# RK05exNew.net
KiCad netlist of a schematic drawn in EAGLE
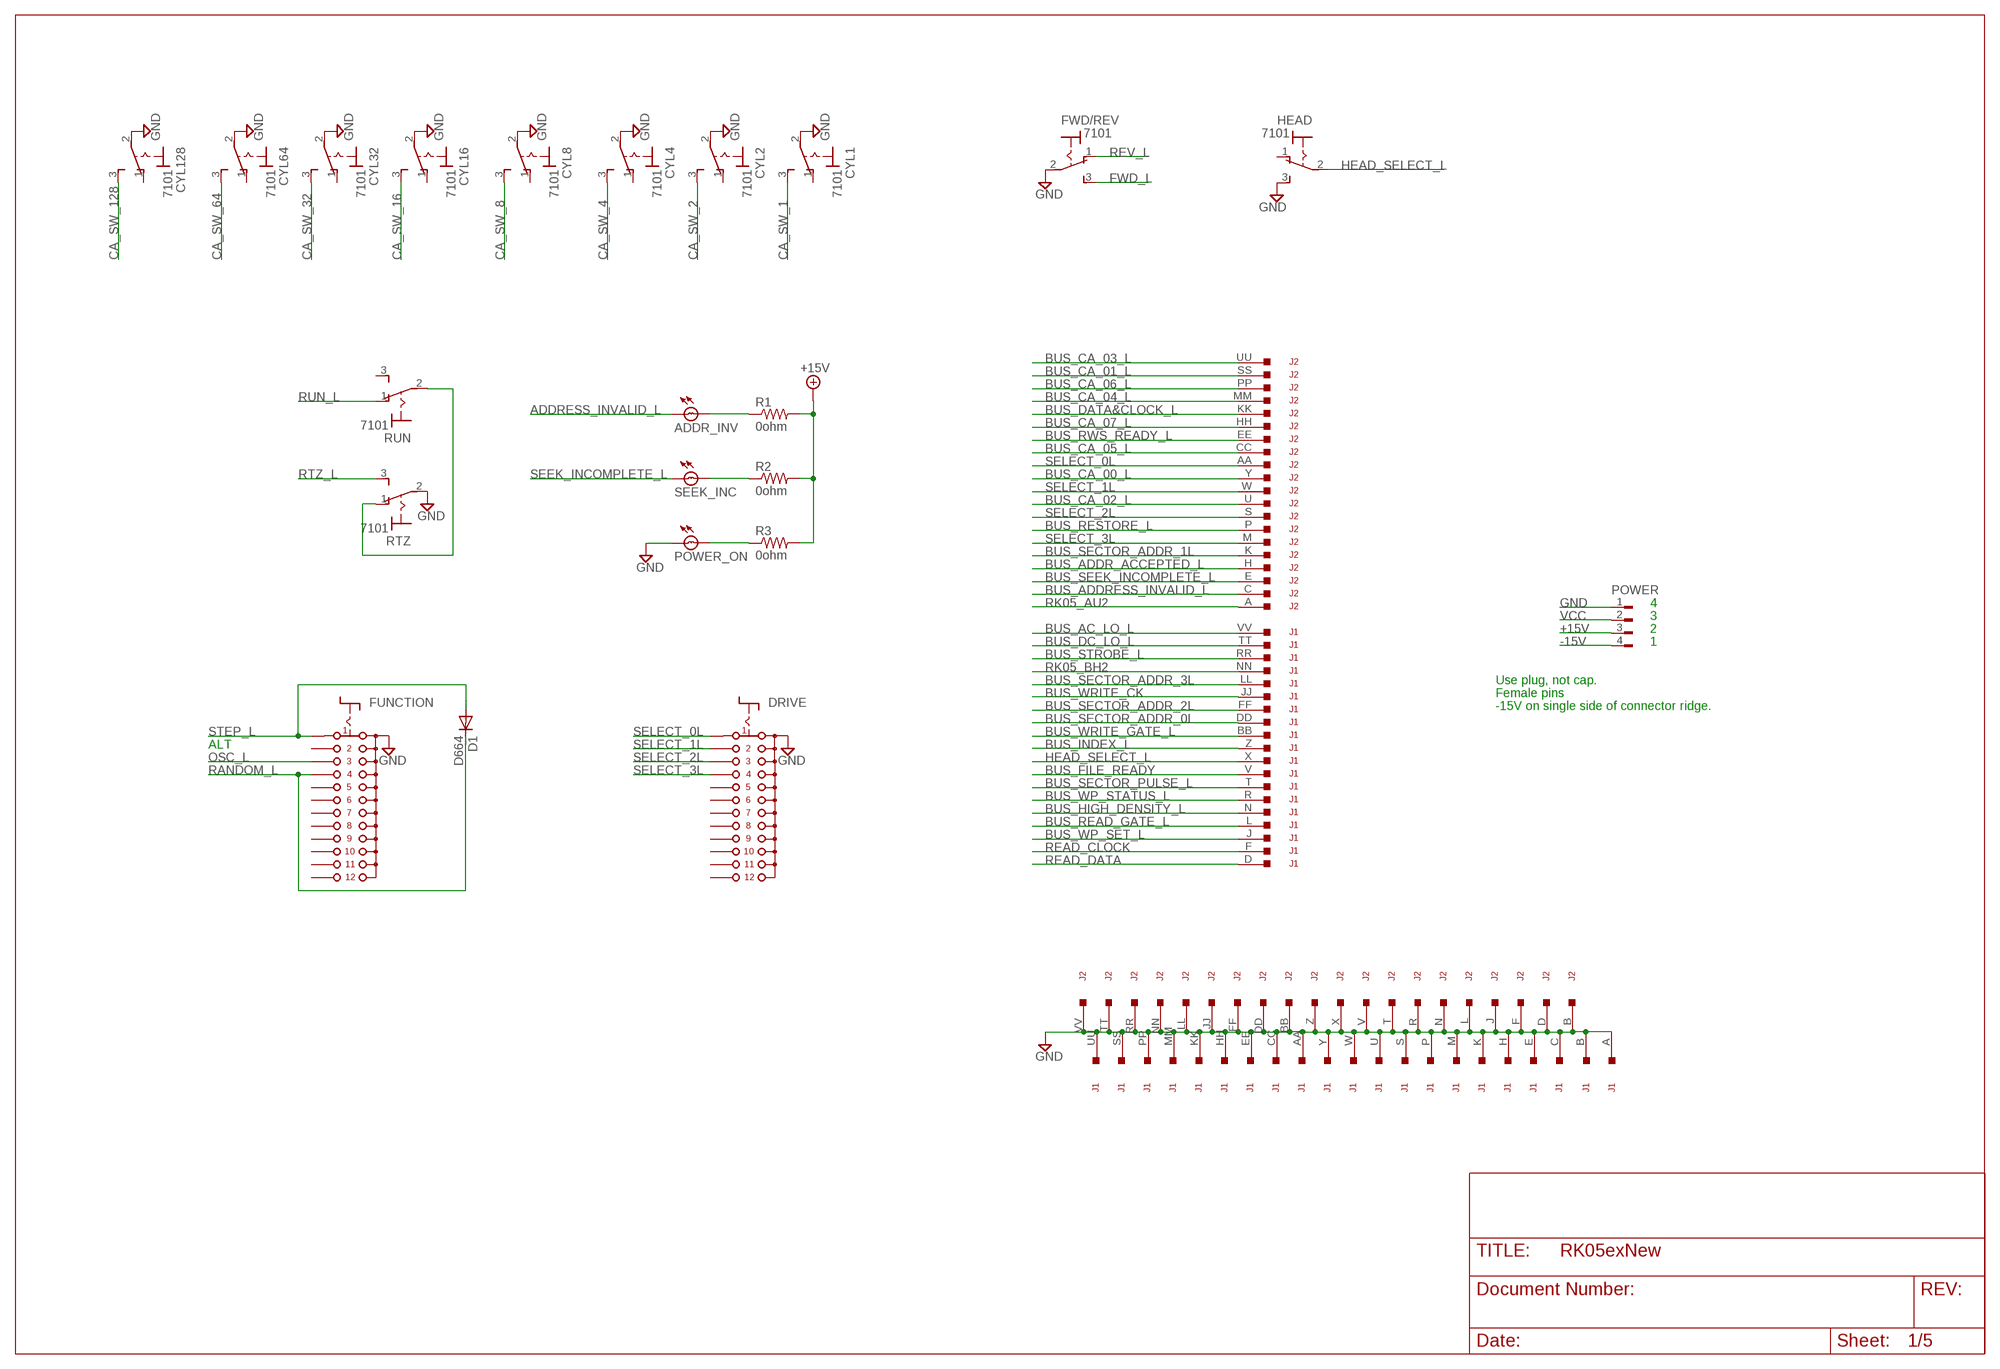
[diagram p0: schematic, sheet 1]
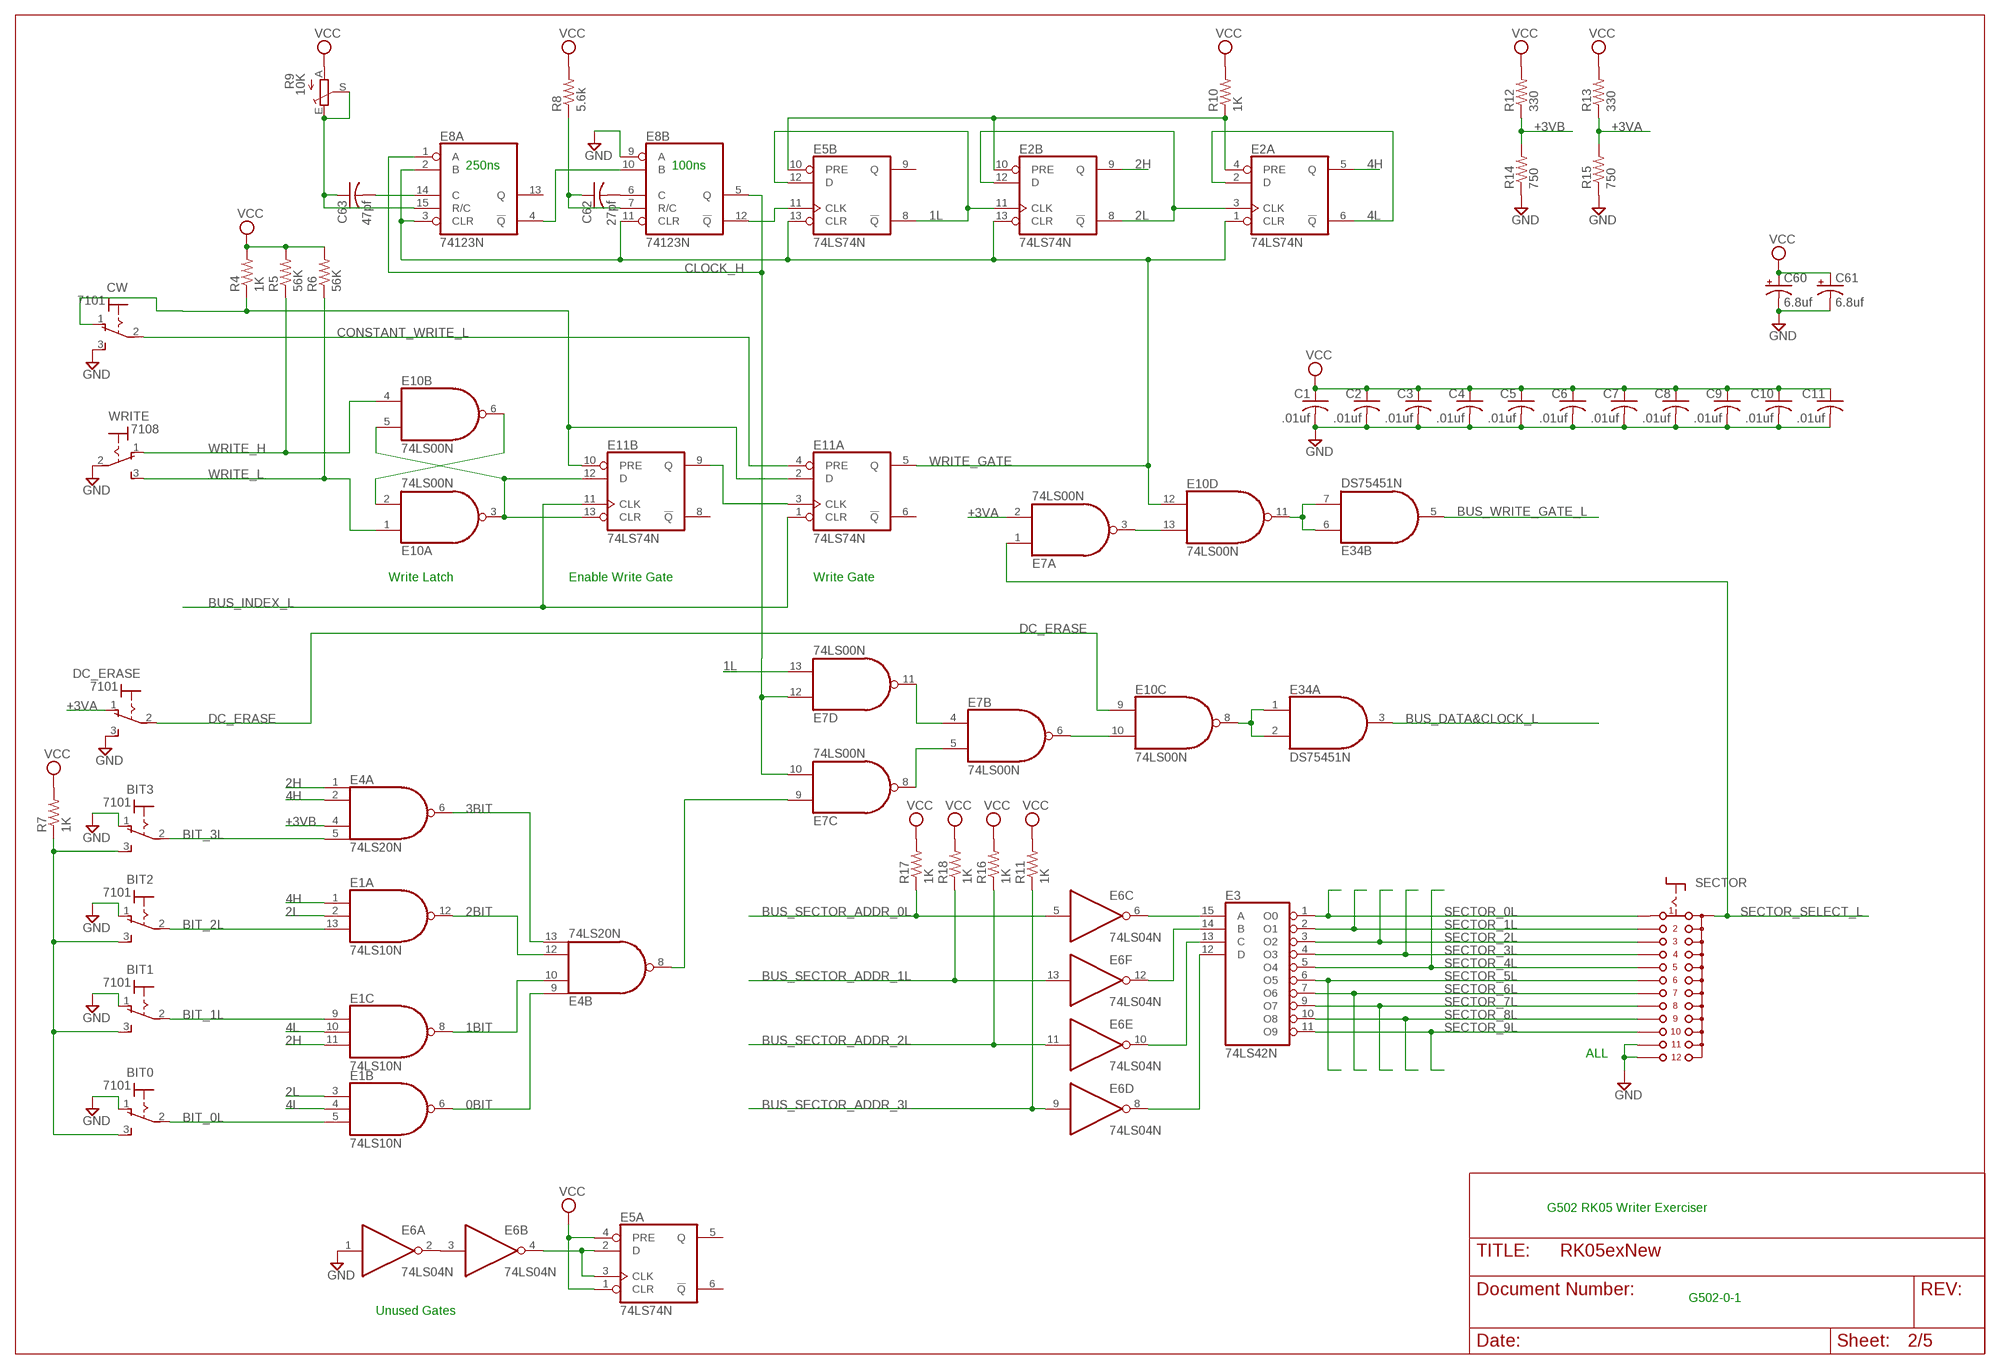
[diagram p1: schematic, sheet 2]
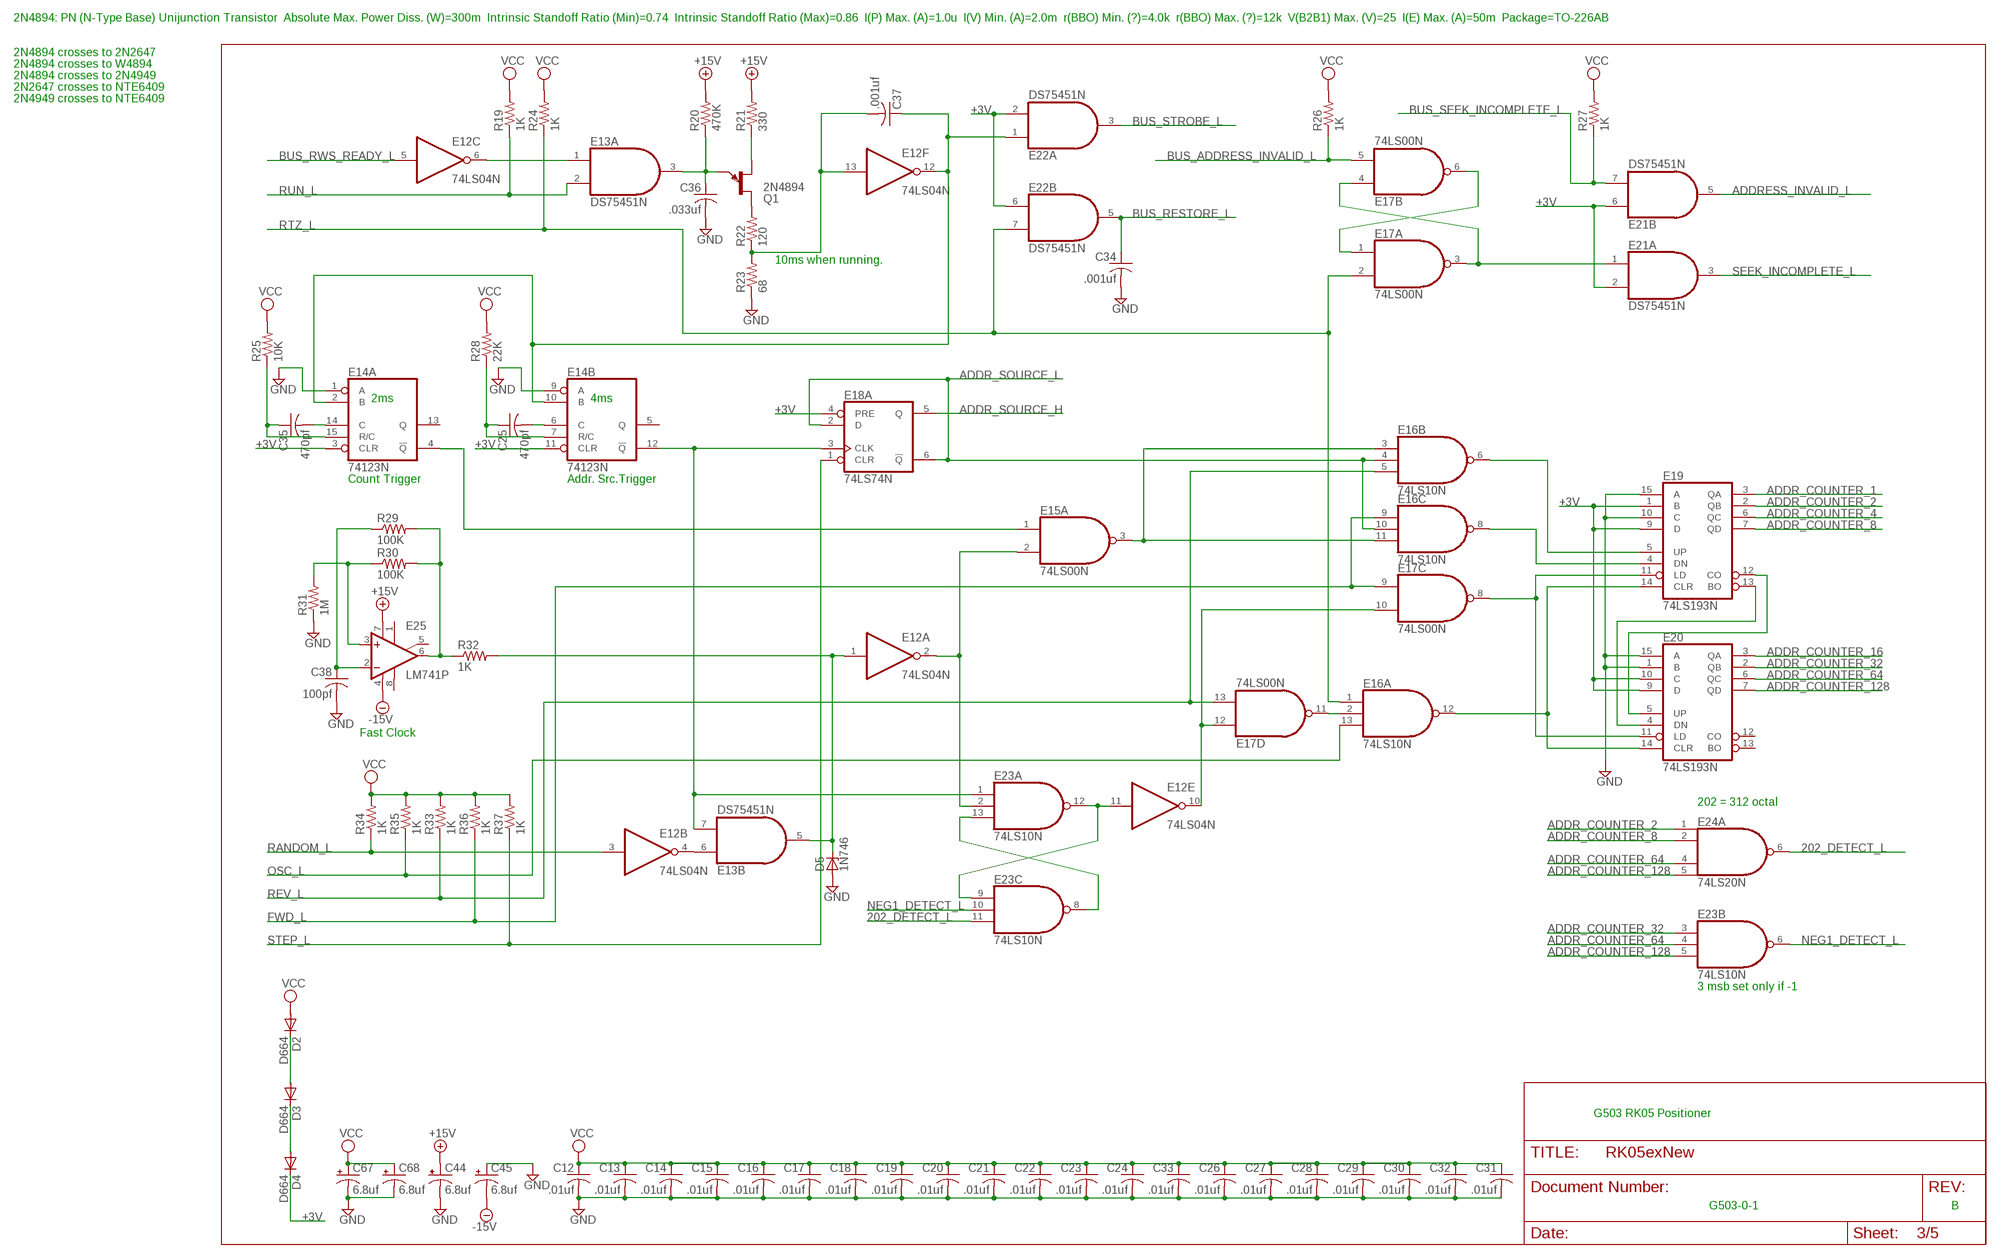
[diagram p2: schematic, sheet 3]
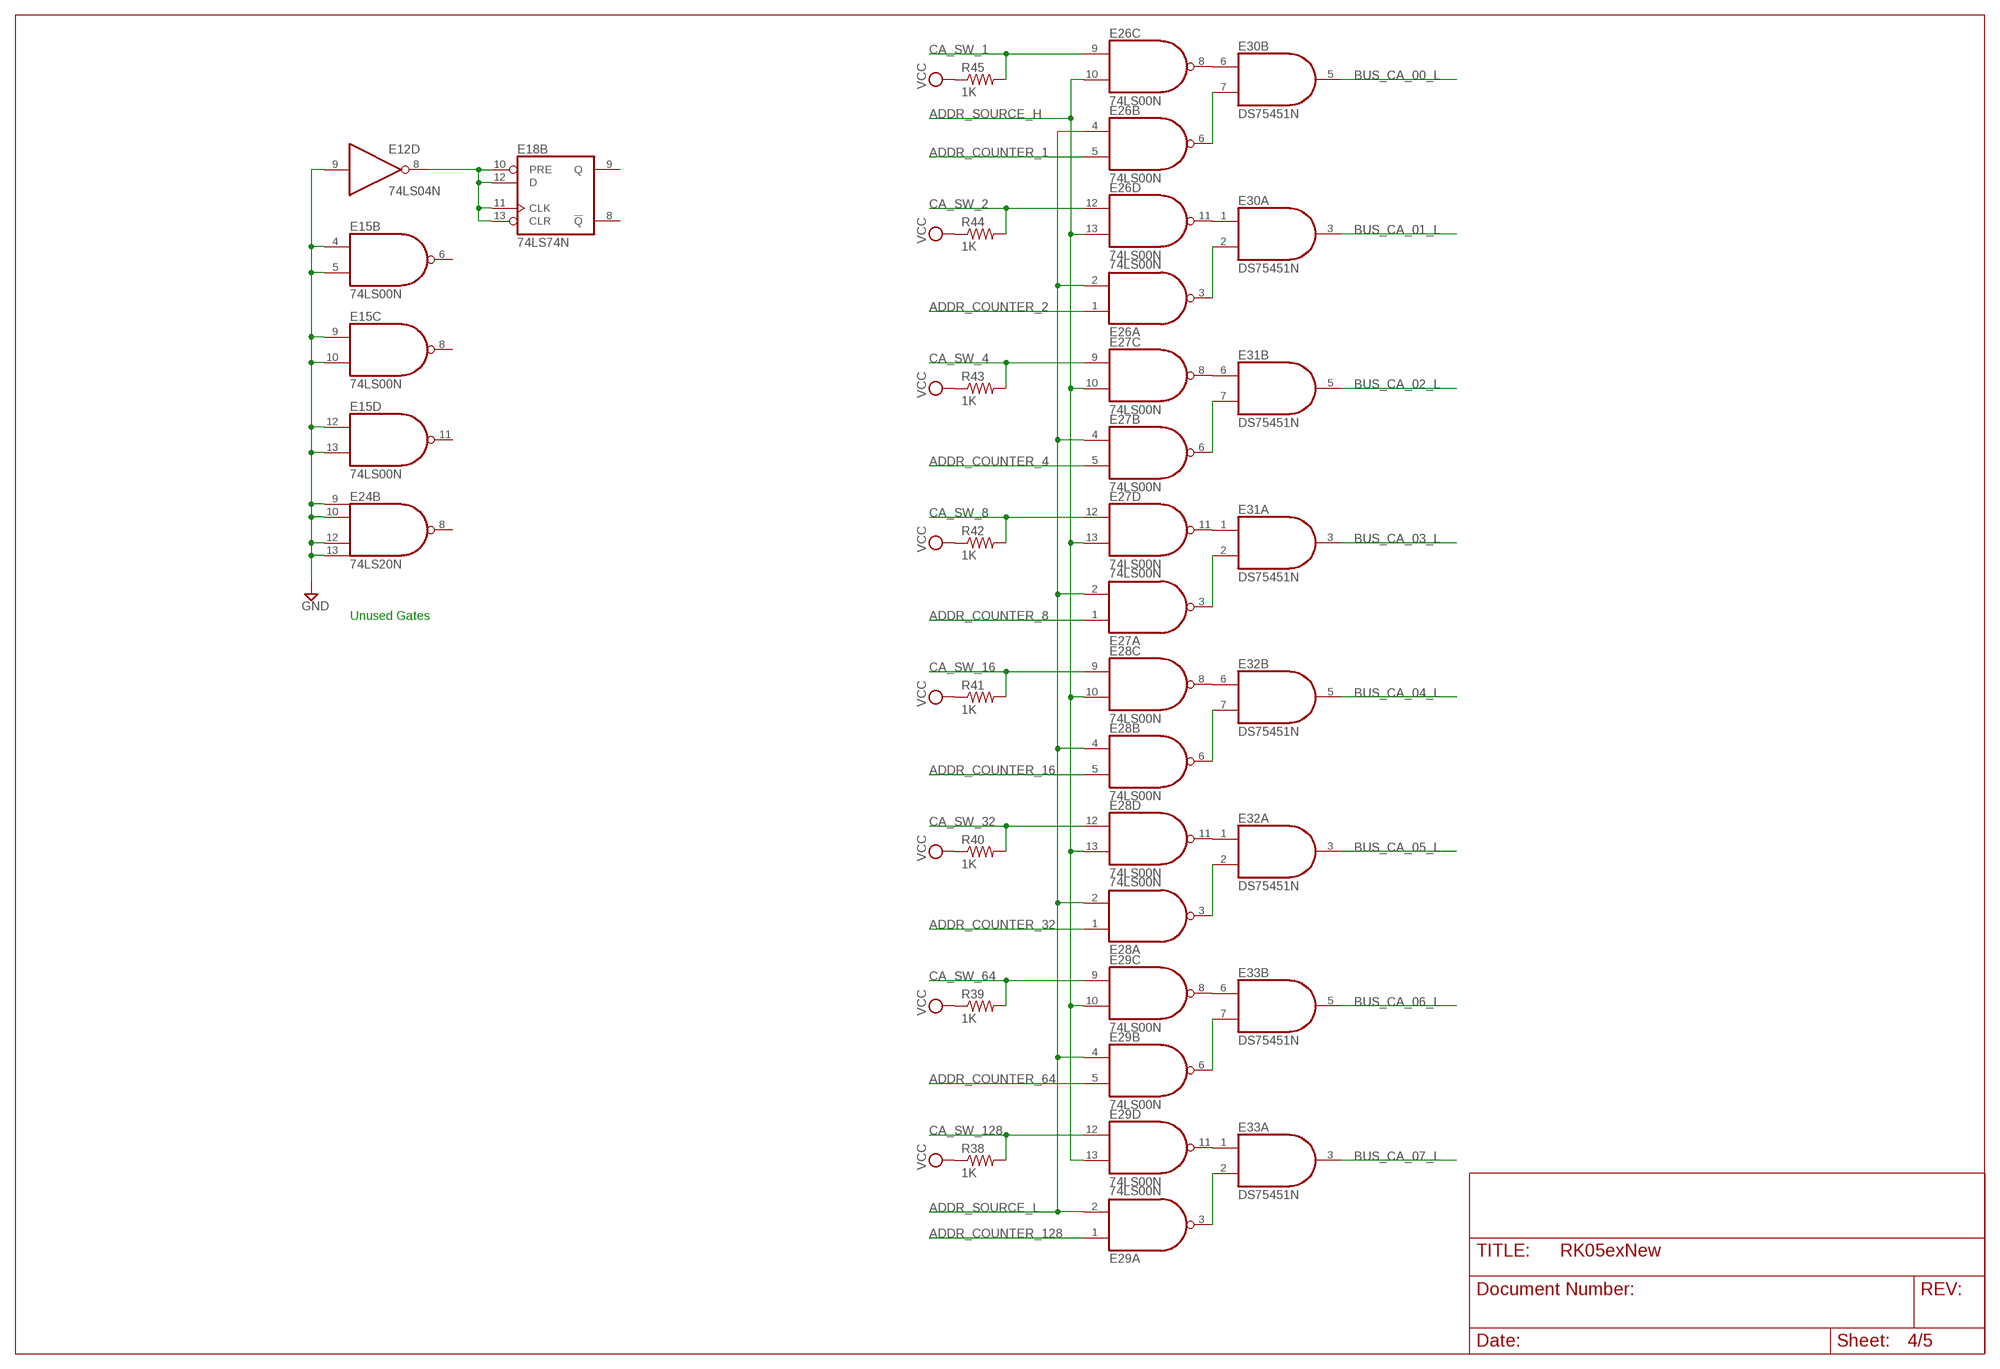
[diagram p3: schematic, sheet 4]
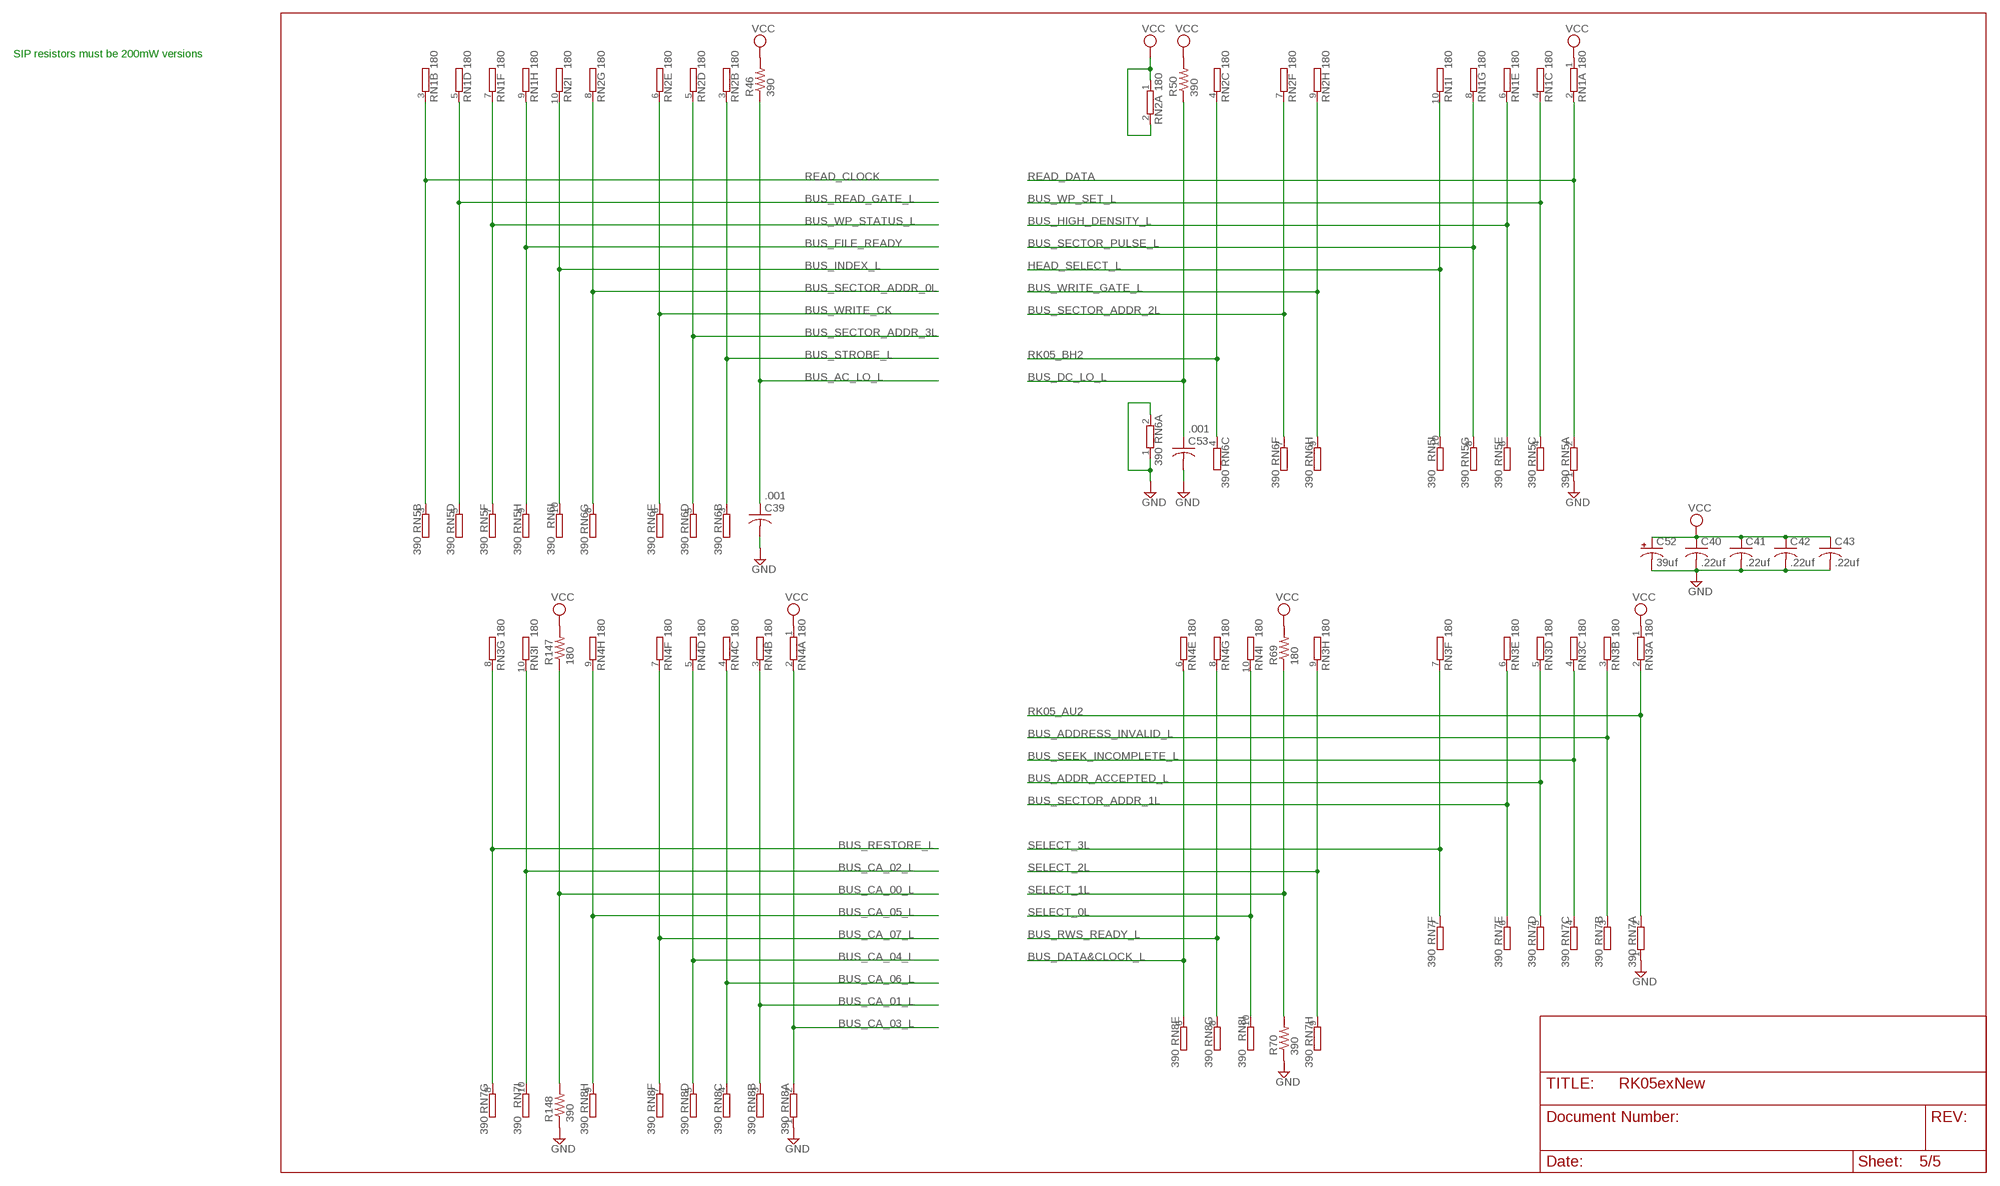
[diagram p4: schematic, sheet 5]

(export (version "E")
  (design (tool "Eeschema 10.0.6"))
  (components
    (comp (ref "E12")
      (value "74LS04N")
      (footprint "eagle-import:DIL14")
      (libsource (lib "eagle-import") (part "7404NLS"))
    )
    (comp (ref "E15")
      (value "74LS00N")
      (footprint "eagle-import:DIL14")
      (libsource (lib "eagle-import") (part "7400NLS"))
    )
    (comp (ref "E18")
      (value "74LS74N")
      (footprint "eagle-import:DIL14")
      (libsource (lib "eagle-import") (part "7474NLS"))
    )
    (comp (ref "E24")
      (value "74LS20N")
      (footprint "eagle-import:DIL14")
      (libsource (lib "eagle-import") (part "7420NLS"))
    )
    (comp (ref "E26")
      (value "74LS00N")
      (footprint "eagle-import:DIL14")
      (libsource (lib "eagle-import") (part "7400NLS"))
    )
    (comp (ref "E27")
      (value "74LS00N")
      (footprint "eagle-import:DIL14")
      (libsource (lib "eagle-import") (part "7400NLS"))
    )
    (comp (ref "E28")
      (value "74LS00N")
      (footprint "eagle-import:DIL14")
      (libsource (lib "eagle-import") (part "7400NLS"))
    )
    (comp (ref "E29")
      (value "74LS00N")
      (footprint "eagle-import:DIL14")
      (libsource (lib "eagle-import") (part "7400NLS"))
    )
    (comp (ref "E30")
      (value "DS75451N")
      (footprint "eagle-import:DIL08")
      (libsource (lib "eagle-import") (part "DS75451N"))
    )
    (comp (ref "E31")
      (value "DS75451N")
      (footprint "eagle-import:DIL08")
      (libsource (lib "eagle-import") (part "DS75451N"))
    )
    (comp (ref "E32")
      (value "DS75451N")
      (footprint "eagle-import:DIL08")
      (libsource (lib "eagle-import") (part "DS75451N"))
    )
    (comp (ref "E33")
      (value "DS75451N")
      (footprint "eagle-import:DIL08")
      (libsource (lib "eagle-import") (part "DS75451N"))
    )
    (comp (ref "R38")
      (value "1K")
      (footprint "eagle-import:0207_10")
      (libsource (lib "eagle-import") (part "R-US_0207/10"))
    )
    (comp (ref "R39")
      (value "1K")
      (footprint "eagle-import:0207_10")
      (libsource (lib "eagle-import") (part "R-US_0207/10"))
    )
    (comp (ref "R40")
      (value "1K")
      (footprint "eagle-import:0207_10")
      (libsource (lib "eagle-import") (part "R-US_0207/10"))
    )
    (comp (ref "R41")
      (value "1K")
      (footprint "eagle-import:0207_10")
      (libsource (lib "eagle-import") (part "R-US_0207/10"))
    )
    (comp (ref "R42")
      (value "1K")
      (footprint "eagle-import:0207_10")
      (libsource (lib "eagle-import") (part "R-US_0207/10"))
    )
    (comp (ref "R43")
      (value "1K")
      (footprint "eagle-import:0207_10")
      (libsource (lib "eagle-import") (part "R-US_0207/10"))
    )
    (comp (ref "R44")
      (value "1K")
      (footprint "eagle-import:0207_10")
      (libsource (lib "eagle-import") (part "R-US_0207/10"))
    )
    (comp (ref "R45")
      (value "1K")
      (footprint "eagle-import:0207_10")
      (libsource (lib "eagle-import") (part "R-US_0207/10"))
    )
    (comp (ref "C12")
      (value ".01uf")
      (footprint "eagle-import:C075-032X103")
      (libsource (lib "eagle-import") (part "C-US075-032X103"))
    )
    (comp (ref "C13")
      (value ".01uf")
      (footprint "eagle-import:C075-032X103")
      (libsource (lib "eagle-import") (part "C-US075-032X103"))
    )
    (comp (ref "C14")
      (value ".01uf")
      (footprint "eagle-import:C075-032X103")
      (libsource (lib "eagle-import") (part "C-US075-032X103"))
    )
    (comp (ref "C15")
      (value ".01uf")
      (footprint "eagle-import:C075-032X103")
      (libsource (lib "eagle-import") (part "C-US075-032X103"))
    )
    (comp (ref "C16")
      (value ".01uf")
      (footprint "eagle-import:C075-032X103")
      (libsource (lib "eagle-import") (part "C-US075-032X103"))
    )
    (comp (ref "C17")
      (value ".01uf")
      (footprint "eagle-import:C075-032X103")
      (libsource (lib "eagle-import") (part "C-US075-032X103"))
    )
    (comp (ref "C18")
      (value ".01uf")
      (footprint "eagle-import:C075-032X103")
      (libsource (lib "eagle-import") (part "C-US075-032X103"))
    )
    (comp (ref "C19")
      (value ".01uf")
      (footprint "eagle-import:C075-032X103")
      (libsource (lib "eagle-import") (part "C-US075-032X103"))
    )
    (comp (ref "C20")
      (value ".01uf")
      (footprint "eagle-import:C075-032X103")
      (libsource (lib "eagle-import") (part "C-US075-032X103"))
    )
    (comp (ref "C21")
      (value ".01uf")
      (footprint "eagle-import:C075-032X103")
      (libsource (lib "eagle-import") (part "C-US075-032X103"))
    )
    (comp (ref "C22")
      (value ".01uf")
      (footprint "eagle-import:C075-032X103")
      (libsource (lib "eagle-import") (part "C-US075-032X103"))
    )
    (comp (ref "C23")
      (value ".01uf")
      (footprint "eagle-import:C075-032X103")
      (libsource (lib "eagle-import") (part "C-US075-032X103"))
    )
    (comp (ref "C24")
      (value ".01uf")
      (footprint "eagle-import:C075-032X103")
      (libsource (lib "eagle-import") (part "C-US075-032X103"))
    )
    (comp (ref "C25")
      (value "470pf")
      (footprint "eagle-import:C075-032X103")
      (libsource (lib "eagle-import") (part "C-US075-032X103"))
    )
    (comp (ref "C26")
      (value ".01uf")
      (footprint "eagle-import:C075-032X103")
      (libsource (lib "eagle-import") (part "C-US075-032X103"))
    )
    (comp (ref "C27")
      (value ".01uf")
      (footprint "eagle-import:C075-032X103")
      (libsource (lib "eagle-import") (part "C-US075-032X103"))
    )
    (comp (ref "C28")
      (value ".01uf")
      (footprint "eagle-import:C075-032X103")
      (libsource (lib "eagle-import") (part "C-US075-032X103"))
    )
    (comp (ref "C29")
      (value ".01uf")
      (footprint "eagle-import:C075-032X103")
      (libsource (lib "eagle-import") (part "C-US075-032X103"))
    )
    (comp (ref "C30")
      (value ".01uf")
      (footprint "eagle-import:C075-032X103")
      (libsource (lib "eagle-import") (part "C-US075-032X103"))
    )
    (comp (ref "C31")
      (value ".01uf")
      (footprint "eagle-import:C075-032X103")
      (libsource (lib "eagle-import") (part "C-US075-032X103"))
    )
    (comp (ref "C32")
      (value ".01uf")
      (footprint "eagle-import:C075-032X103")
      (libsource (lib "eagle-import") (part "C-US075-032X103"))
    )
    (comp (ref "C33")
      (value ".01uf")
      (footprint "eagle-import:C075-032X103")
      (libsource (lib "eagle-import") (part "C-US075-032X103"))
    )
    (comp (ref "C34")
      (value ".001uf")
      (footprint "eagle-import:C075-032X103")
      (libsource (lib "eagle-import") (part "C-US075-032X103"))
    )
    (comp (ref "C35")
      (value "470pf")
      (footprint "eagle-import:C075-032X103")
      (libsource (lib "eagle-import") (part "C-US075-032X103"))
    )
    (comp (ref "C36")
      (value ".033uf")
      (footprint "eagle-import:C075-032X103")
      (libsource (lib "eagle-import") (part "C-US075-032X103"))
    )
    (comp (ref "C37")
      (value ".001uf")
      (footprint "eagle-import:C075-032X103")
      (libsource (lib "eagle-import") (part "C-US075-032X103"))
    )
    (comp (ref "C38")
      (value "100pf")
      (footprint "eagle-import:C075-032X103")
      (libsource (lib "eagle-import") (part "C-US075-032X103"))
    )
    (comp (ref "C44")
      (value "6.8uf")
      (footprint "eagle-import:E15-5")
      (libsource (lib "eagle-import") (part "CPOL-USE15-5AXIAL"))
    )
    (comp (ref "C45")
      (value "6.8uf")
      (footprint "eagle-import:E15-5")
      (libsource (lib "eagle-import") (part "CPOL-USE15-5AXIAL"))
    )
    (comp (ref "C67")
      (value "6.8uf")
      (footprint "eagle-import:E15-5")
      (libsource (lib "eagle-import") (part "CPOL-USE15-5AXIAL"))
    )
    (comp (ref "C68")
      (value "6.8uf")
      (footprint "eagle-import:E15-5")
      (libsource (lib "eagle-import") (part "CPOL-USE15-5AXIAL"))
    )
    (comp (ref "D2")
      (value "D664")
      (footprint "eagle-import:DO35-10")
      (libsource (lib "eagle-import") (part "1N4148DO35-10"))
    )
    (comp (ref "D3")
      (value "D664")
      (footprint "eagle-import:DO35-10")
      (libsource (lib "eagle-import") (part "1N4148DO35-10"))
    )
    (comp (ref "D4")
      (value "D664")
      (footprint "eagle-import:DO35-10")
      (libsource (lib "eagle-import") (part "1N4148DO35-10"))
    )
    (comp (ref "D5")
      (value "1N746")
      (footprint "eagle-import:DO35Z10")
      (libsource (lib "eagle-import") (part "ZENER-DIODEDO35Z10"))
    )
    (comp (ref "E13")
      (value "DS75451N")
      (footprint "eagle-import:DIL08")
      (libsource (lib "eagle-import") (part "DS75451N"))
    )
    (comp (ref "E14")
      (value "74123N")
      (footprint "eagle-import:DIL16")
      (libsource (lib "eagle-import") (part "74123N"))
    )
    (comp (ref "E16")
      (value "74LS10N")
      (footprint "eagle-import:DIL14")
      (libsource (lib "eagle-import") (part "7410NLS"))
    )
    (comp (ref "E17")
      (value "74LS00N")
      (footprint "eagle-import:DIL14")
      (libsource (lib "eagle-import") (part "7400NLS"))
    )
    (comp (ref "E19")
      (value "74LS193N")
      (footprint "eagle-import:DIL16")
      (libsource (lib "eagle-import") (part "74193NLS"))
    )
    (comp (ref "E20")
      (value "74LS193N")
      (footprint "eagle-import:DIL16")
      (libsource (lib "eagle-import") (part "74193NLS"))
    )
    (comp (ref "E21")
      (value "DS75451N")
      (footprint "eagle-import:DIL08")
      (libsource (lib "eagle-import") (part "DS75451N"))
    )
    (comp (ref "E22")
      (value "DS75451N")
      (footprint "eagle-import:DIL08")
      (libsource (lib "eagle-import") (part "DS75451N"))
    )
    (comp (ref "E23")
      (value "74LS10N")
      (footprint "eagle-import:DIL14")
      (libsource (lib "eagle-import") (part "7410NLS"))
    )
    (comp (ref "E25")
      (value "LM741P")
      (footprint "eagle-import:DIL08")
      (libsource (lib "eagle-import") (part "741PLM"))
    )
    (comp (ref "Q1")
      (value "2N4894")
      (footprint "eagle-import:TO92E")
      (libsource (lib "eagle-import") (part "2N4870"))
    )
    (comp (ref "R19")
      (value "1K")
      (footprint "eagle-import:0207_10")
      (libsource (lib "eagle-import") (part "R-US_0207/10"))
    )
    (comp (ref "R20")
      (value "470K")
      (footprint "eagle-import:0207_10")
      (libsource (lib "eagle-import") (part "R-US_0207/10"))
    )
    (comp (ref "R21")
      (value "330")
      (footprint "eagle-import:0207_10")
      (libsource (lib "eagle-import") (part "R-US_0207/10"))
    )
    (comp (ref "R22")
      (value "120")
      (footprint "eagle-import:0207_10")
      (libsource (lib "eagle-import") (part "R-US_0207/10"))
    )
    (comp (ref "R23")
      (value "68")
      (footprint "eagle-import:0207_10")
      (libsource (lib "eagle-import") (part "R-US_0207/10"))
    )
    (comp (ref "R24")
      (value "1K")
      (footprint "eagle-import:0207_10")
      (libsource (lib "eagle-import") (part "R-US_0207/10"))
    )
    (comp (ref "R25")
      (value "10K")
      (footprint "eagle-import:0207_10")
      (libsource (lib "eagle-import") (part "R-US_0207/10"))
    )
    (comp (ref "R26")
      (value "1K")
      (footprint "eagle-import:0207_10")
      (libsource (lib "eagle-import") (part "R-US_0207/10"))
    )
    (comp (ref "R27")
      (value "1K")
      (footprint "eagle-import:0207_10")
      (libsource (lib "eagle-import") (part "R-US_0207/10"))
    )
    (comp (ref "R28")
      (value "22K")
      (footprint "eagle-import:0207_10")
      (libsource (lib "eagle-import") (part "R-US_0207/10"))
    )
    (comp (ref "R29")
      (value "100K")
      (footprint "eagle-import:0207_10")
      (libsource (lib "eagle-import") (part "R-US_0207/10"))
    )
    (comp (ref "R30")
      (value "100K")
      (footprint "eagle-import:0207_10")
      (libsource (lib "eagle-import") (part "R-US_0207/10"))
    )
    (comp (ref "R31")
      (value "1M")
      (footprint "eagle-import:0207_10")
      (libsource (lib "eagle-import") (part "R-US_0207/10"))
    )
    (comp (ref "R32")
      (value "1K")
      (footprint "eagle-import:0207_10")
      (libsource (lib "eagle-import") (part "R-US_0207/10"))
    )
    (comp (ref "R33")
      (value "1K")
      (footprint "eagle-import:0207_10")
      (libsource (lib "eagle-import") (part "R-US_0207/10"))
    )
    (comp (ref "R34")
      (value "1K")
      (footprint "eagle-import:0207_10")
      (libsource (lib "eagle-import") (part "R-US_0207/10"))
    )
    (comp (ref "R35")
      (value "1K")
      (footprint "eagle-import:0207_10")
      (libsource (lib "eagle-import") (part "R-US_0207/10"))
    )
    (comp (ref "R36")
      (value "1K")
      (footprint "eagle-import:0207_10")
      (libsource (lib "eagle-import") (part "R-US_0207/10"))
    )
    (comp (ref "R37")
      (value "1K")
      (footprint "eagle-import:0207_10")
      (libsource (lib "eagle-import") (part "R-US_0207/10"))
    )
    (comp (ref "BIT0")
      (value "7101")
      (footprint "eagle-import:7109MD9V3")
      (libsource (lib "eagle-import") (part "710X"))
    )
    (comp (ref "BIT1")
      (value "7101")
      (footprint "eagle-import:7109MD9V3")
      (libsource (lib "eagle-import") (part "710X"))
    )
    (comp (ref "BIT2")
      (value "7101")
      (footprint "eagle-import:7109MD9V3")
      (libsource (lib "eagle-import") (part "710X"))
    )
    (comp (ref "BIT3")
      (value "7101")
      (footprint "eagle-import:7109MD9V3")
      (libsource (lib "eagle-import") (part "710X"))
    )
    (comp (ref "C1")
      (value ".01uf")
      (footprint "eagle-import:C075-032X103")
      (libsource (lib "eagle-import") (part "C-US075-032X103"))
    )
    (comp (ref "C2")
      (value ".01uf")
      (footprint "eagle-import:C075-032X103")
      (libsource (lib "eagle-import") (part "C-US075-032X103"))
    )
    (comp (ref "C3")
      (value ".01uf")
      (footprint "eagle-import:C075-032X103")
      (libsource (lib "eagle-import") (part "C-US075-032X103"))
    )
    (comp (ref "C4")
      (value ".01uf")
      (footprint "eagle-import:C075-032X103")
      (libsource (lib "eagle-import") (part "C-US075-032X103"))
    )
    (comp (ref "C5")
      (value ".01uf")
      (footprint "eagle-import:C075-032X103")
      (libsource (lib "eagle-import") (part "C-US075-032X103"))
    )
    (comp (ref "C6")
      (value ".01uf")
      (footprint "eagle-import:C075-032X103")
      (libsource (lib "eagle-import") (part "C-US075-032X103"))
    )
    (comp (ref "C7")
      (value ".01uf")
      (footprint "eagle-import:C075-032X103")
      (libsource (lib "eagle-import") (part "C-US075-032X103"))
    )
    (comp (ref "C8")
      (value ".01uf")
      (footprint "eagle-import:C075-032X103")
      (libsource (lib "eagle-import") (part "C-US075-032X103"))
    )
    (comp (ref "C9")
      (value ".01uf")
      (footprint "eagle-import:C075-032X103")
      (libsource (lib "eagle-import") (part "C-US075-032X103"))
    )
    (comp (ref "C10")
      (value ".01uf")
      (footprint "eagle-import:C075-032X103")
      (libsource (lib "eagle-import") (part "C-US075-032X103"))
    )
    (comp (ref "C11")
      (value ".01uf")
      (footprint "eagle-import:C075-032X103")
      (libsource (lib "eagle-import") (part "C-US075-032X103"))
    )
    (comp (ref "C60")
      (value "6.8uf")
      (footprint "eagle-import:E15-5")
      (libsource (lib "eagle-import") (part "CPOL-USE15-5AXIAL"))
    )
    (comp (ref "C61")
      (value "6.8uf")
      (footprint "eagle-import:E15-5")
      (libsource (lib "eagle-import") (part "CPOL-USE15-5AXIAL"))
    )
    (comp (ref "C62")
      (value "27pf")
      (footprint "eagle-import:C075-032X103")
      (libsource (lib "eagle-import") (part "C-US075-032X103"))
    )
    (comp (ref "C63")
      (value "47pf")
      (footprint "eagle-import:C075-032X103")
      (libsource (lib "eagle-import") (part "C-US075-032X103"))
    )
    (comp (ref "CW")
      (value "7101")
      (footprint "eagle-import:7109MD9V3")
      (libsource (lib "eagle-import") (part "710X"))
    )
    (comp (ref "DC_ERASE")
      (value "7101")
      (footprint "eagle-import:7109MD9V3")
      (libsource (lib "eagle-import") (part "710X"))
    )
    (comp (ref "E1")
      (value "74LS10N")
      (footprint "eagle-import:DIL14")
      (libsource (lib "eagle-import") (part "7410NLS"))
    )
    (comp (ref "E2")
      (value "74LS74N")
      (footprint "eagle-import:DIL14")
      (libsource (lib "eagle-import") (part "7474NLS"))
    )
    (comp (ref "E3")
      (value "74LS42N")
      (footprint "eagle-import:DIL16")
      (libsource (lib "eagle-import") (part "7442NLS"))
    )
    (comp (ref "E4")
      (value "74LS20N")
      (footprint "eagle-import:DIL14")
      (libsource (lib "eagle-import") (part "7420NLS"))
    )
    (comp (ref "E5")
      (value "74LS74N")
      (footprint "eagle-import:DIL14")
      (libsource (lib "eagle-import") (part "7474NLS"))
    )
    (comp (ref "E6")
      (value "74LS04N")
      (footprint "eagle-import:DIL14")
      (libsource (lib "eagle-import") (part "7404NLS"))
    )
    (comp (ref "E7")
      (value "74LS00N")
      (footprint "eagle-import:DIL14")
      (libsource (lib "eagle-import") (part "7400NLS"))
    )
    (comp (ref "E8")
      (value "74123N")
      (footprint "eagle-import:DIL16")
      (libsource (lib "eagle-import") (part "74123N"))
    )
    (comp (ref "E10")
      (value "74LS00N")
      (footprint "eagle-import:DIL14")
      (libsource (lib "eagle-import") (part "7400NLS"))
    )
    (comp (ref "E11")
      (value "74LS74N")
      (footprint "eagle-import:DIL14")
      (libsource (lib "eagle-import") (part "7474NLS"))
    )
    (comp (ref "E34")
      (value "DS75451N")
      (footprint "eagle-import:DIL08")
      (libsource (lib "eagle-import") (part "DS75451N"))
    )
    (comp (ref "R4")
      (value "1K")
      (footprint "eagle-import:0207_10")
      (libsource (lib "eagle-import") (part "R-US_0207/10"))
    )
    (comp (ref "R5")
      (value "56K")
      (footprint "eagle-import:0207_10")
      (libsource (lib "eagle-import") (part "R-US_0207/10"))
    )
    (comp (ref "R6")
      (value "56K")
      (footprint "eagle-import:0207_10")
      (libsource (lib "eagle-import") (part "R-US_0207/10"))
    )
    (comp (ref "R7")
      (value "1K")
      (footprint "eagle-import:0207_10")
      (libsource (lib "eagle-import") (part "R-US_0207/10"))
    )
    (comp (ref "R8")
      (value "5.6k")
      (footprint "eagle-import:0207_10")
      (libsource (lib "eagle-import") (part "R-US_0207/10"))
    )
    (comp (ref "R9")
      (value "10K")
      (footprint "eagle-import:SP19L")
      (libsource (lib "eagle-import") (part "TRIM_EU-B90P"))
    )
    (comp (ref "R10")
      (value "1K")
      (footprint "eagle-import:0207_10")
      (libsource (lib "eagle-import") (part "R-US_0207/10"))
    )
    (comp (ref "R11")
      (value "1K")
      (footprint "eagle-import:0207_10")
      (libsource (lib "eagle-import") (part "R-US_0207/10"))
    )
    (comp (ref "R12")
      (value "330")
      (footprint "eagle-import:0207_10")
      (libsource (lib "eagle-import") (part "R-US_0207/10"))
    )
    (comp (ref "R13")
      (value "330")
      (footprint "eagle-import:0207_10")
      (libsource (lib "eagle-import") (part "R-US_0207/10"))
    )
    (comp (ref "R14")
      (value "750")
      (footprint "eagle-import:0207_10")
      (libsource (lib "eagle-import") (part "R-US_0207/10"))
    )
    (comp (ref "R15")
      (value "750")
      (footprint "eagle-import:0207_10")
      (libsource (lib "eagle-import") (part "R-US_0207/10"))
    )
    (comp (ref "R16")
      (value "1K")
      (footprint "eagle-import:0207_10")
      (libsource (lib "eagle-import") (part "R-US_0207/10"))
    )
    (comp (ref "R17")
      (value "1K")
      (footprint "eagle-import:0207_10")
      (libsource (lib "eagle-import") (part "R-US_0207/10"))
    )
    (comp (ref "R18")
      (value "1K")
      (footprint "eagle-import:0207_10")
      (libsource (lib "eagle-import") (part "R-US_0207/10"))
    )
    (comp (ref "SECTOR")
      (value "CK101X12")
      (footprint "eagle-import:CK101X12")
      (libsource (lib "eagle-import") (part "CK101X12"))
    )
    (comp (ref "WRITE")
      (value "7108")
      (footprint "eagle-import:7109MD9V3")
      (libsource (lib "eagle-import") (part "710X"))
    )
    (comp (ref "ADDR_INV")
      (value "BULB")
      (footprint "eagle-import:BULB")
      (libsource (lib "eagle-import") (part "BULB"))
    )
    (comp (ref "CYL1")
      (value "7101")
      (footprint "eagle-import:7109MD9V3")
      (libsource (lib "eagle-import") (part "710X"))
    )
    (comp (ref "CYL2")
      (value "7101")
      (footprint "eagle-import:7109MD9V3")
      (libsource (lib "eagle-import") (part "710X"))
    )
    (comp (ref "CYL4")
      (value "7101")
      (footprint "eagle-import:7109MD9V3")
      (libsource (lib "eagle-import") (part "710X"))
    )
    (comp (ref "CYL8")
      (value "7101")
      (footprint "eagle-import:7109MD9V3")
      (libsource (lib "eagle-import") (part "710X"))
    )
    (comp (ref "CYL16")
      (value "7101")
      (footprint "eagle-import:7109MD9V3")
      (libsource (lib "eagle-import") (part "710X"))
    )
    (comp (ref "CYL32")
      (value "7101")
      (footprint "eagle-import:7109MD9V3")
      (libsource (lib "eagle-import") (part "710X"))
    )
    (comp (ref "CYL64")
      (value "7101")
      (footprint "eagle-import:7109MD9V3")
      (libsource (lib "eagle-import") (part "710X"))
    )
    (comp (ref "CYL128")
      (value "7101")
      (footprint "eagle-import:7109MD9V3")
      (libsource (lib "eagle-import") (part "710X"))
    )
    (comp (ref "D1")
      (value "D664")
      (footprint "eagle-import:DO35-10")
      (libsource (lib "eagle-import") (part "1N4148DO35-10"))
    )
    (comp (ref "DRIVE")
      (value "CK101X12")
      (footprint "eagle-import:CK101X12")
      (libsource (lib "eagle-import") (part "CK101X12"))
    )
    (comp (ref "FUNCTION")
      (value "CK101X12")
      (footprint "eagle-import:CK101X12")
      (libsource (lib "eagle-import") (part "CK101X12"))
    )
    (comp (ref "FWD/REV")
      (value "7101")
      (footprint "eagle-import:7109MD9V3")
      (libsource (lib "eagle-import") (part "710X"))
    )
    (comp (ref "HEAD")
      (value "7101")
      (footprint "eagle-import:7109MD9V3")
      (libsource (lib "eagle-import") (part "710X"))
    )
    (comp (ref "J1")
      (value "DEC40PINSV")
      (footprint "eagle-import:DEC40PINV")
      (libsource (lib "eagle-import") (part "DEC40PINSV"))
    )
    (comp (ref "J2")
      (value "DEC40PINSV")
      (footprint "eagle-import:DEC40PINV")
      (libsource (lib "eagle-import") (part "DEC40PINSV"))
    )
    (comp (ref "POWER")
      (value "FLOPPY-4")
      (footprint "eagle-import:FLOPPY-4")
      (libsource (lib "eagle-import") (part "FLOPPY-4"))
    )
    (comp (ref "POWER_ON")
      (value "BULB")
      (footprint "eagle-import:BULB")
      (libsource (lib "eagle-import") (part "BULB"))
    )
    (comp (ref "R1")
      (value "0ohm")
      (footprint "eagle-import:0207_10")
      (libsource (lib "eagle-import") (part "R-US_0207/10"))
    )
    (comp (ref "R2")
      (value "0ohm")
      (footprint "eagle-import:0207_10")
      (libsource (lib "eagle-import") (part "R-US_0207/10"))
    )
    (comp (ref "R3")
      (value "0ohm")
      (footprint "eagle-import:0207_10")
      (libsource (lib "eagle-import") (part "R-US_0207/10"))
    )
    (comp (ref "RTZ")
      (value "7101")
      (footprint "eagle-import:7109MD9V3")
      (libsource (lib "eagle-import") (part "710X"))
    )
    (comp (ref "RUN")
      (value "7101")
      (footprint "eagle-import:7109MD9V3")
      (libsource (lib "eagle-import") (part "710X"))
    )
    (comp (ref "SEEK_INC")
      (value "BULB")
      (footprint "eagle-import:BULB")
      (libsource (lib "eagle-import") (part "BULB"))
    )
    (comp (ref "C39")
      (value ".001")
      (footprint "eagle-import:C050-025X075")
      (libsource (lib "eagle-import") (part "C-US050-025X075"))
    )
    (comp (ref "C40")
      (value ".22uf")
      (footprint "eagle-import:C050-025X075")
      (libsource (lib "eagle-import") (part "C-US050-025X075"))
    )
    (comp (ref "C41")
      (value ".22uf")
      (footprint "eagle-import:C050-025X075")
      (libsource (lib "eagle-import") (part "C-US050-025X075"))
    )
    (comp (ref "C42")
      (value ".22uf")
      (footprint "eagle-import:C050-025X075")
      (libsource (lib "eagle-import") (part "C-US050-025X075"))
    )
    (comp (ref "C43")
      (value ".22uf")
      (footprint "eagle-import:C075-032X103")
      (libsource (lib "eagle-import") (part "C-US075-032X103"))
    )
    (comp (ref "C52")
      (value "39uf")
      (footprint "eagle-import:E15-5")
      (libsource (lib "eagle-import") (part "CPOL-USE15-5AXIAL"))
    )
    (comp (ref "C53")
      (value ".001")
      (footprint "eagle-import:C075-032X103")
      (libsource (lib "eagle-import") (part "C-US075-032X103"))
    )
    (comp (ref "R46")
      (value "390")
      (footprint "eagle-import:0207_10")
      (libsource (lib "eagle-import") (part "R-US_0207/10"))
    )
    (comp (ref "R50")
      (value "390")
      (footprint "eagle-import:0207_10")
      (libsource (lib "eagle-import") (part "R-US_0207/10"))
    )
    (comp (ref "R69")
      (value "180")
      (footprint "eagle-import:0207_10")
      (libsource (lib "eagle-import") (part "R-US_0207/10"))
    )
    (comp (ref "R70")
      (value "390")
      (footprint "eagle-import:0207_10")
      (libsource (lib "eagle-import") (part "R-US_0207/10"))
    )
    (comp (ref "R147")
      (value "180")
      (footprint "eagle-import:0207_10")
      (libsource (lib "eagle-import") (part "R-US_0207/10"))
    )
    (comp (ref "R148")
      (value "390")
      (footprint "eagle-import:0207_10")
      (libsource (lib "eagle-import") (part "R-US_0207/10"))
    )
    (comp (ref "RN1")
      (value "180")
      (footprint "eagle-import:SIL10")
      (libsource (lib "eagle-import") (part "GE09R"))
    )
    (comp (ref "RN2")
      (value "180")
      (footprint "eagle-import:SIL10")
      (libsource (lib "eagle-import") (part "GE09R"))
    )
    (comp (ref "RN3")
      (value "180")
      (footprint "eagle-import:SIL10")
      (libsource (lib "eagle-import") (part "GE09R"))
    )
    (comp (ref "RN4")
      (value "180")
      (footprint "eagle-import:SIL10")
      (libsource (lib "eagle-import") (part "GE09R"))
    )
    (comp (ref "RN5")
      (value "390")
      (footprint "eagle-import:SIL10")
      (libsource (lib "eagle-import") (part "GE09R"))
    )
    (comp (ref "RN6")
      (value "390")
      (footprint "eagle-import:SIL10")
      (libsource (lib "eagle-import") (part "GE09R"))
    )
    (comp (ref "RN7")
      (value "390")
      (footprint "eagle-import:SIL10")
      (libsource (lib "eagle-import") (part "GE09R"))
    )
    (comp (ref "RN8")
      (value "390")
      (footprint "eagle-import:SIL10")
      (libsource (lib "eagle-import") (part "GE09R"))
    )
  )
  (nets
    (net (code "1") (name "+3V") (class "Default")
      (node (ref "D4") (pin "C") (pinfunction "C_C") (pintype "passive"))
      (node (ref "E14") (pin "11") (pinfunction "CLR_11") (pintype "input"))
      (node (ref "E14") (pin "3") (pinfunction "CLR_3") (pintype "input"))
      (node (ref "E18") (pin "4") (pinfunction "PRE_4") (pintype "input"))
      (node (ref "E19") (pin "1") (pinfunction "B_1") (pintype "input"))
      (node (ref "E19") (pin "9") (pinfunction "D_9") (pintype "input"))
      (node (ref "E20") (pin "10") (pinfunction "C_10") (pintype "input"))
      (node (ref "E20") (pin "9") (pinfunction "D_9") (pintype "input"))
      (node (ref "E21") (pin "2") (pinfunction "I1_2") (pintype "input"))
      (node (ref "E21") (pin "6") (pinfunction "I0_6") (pintype "input"))
      (node (ref "E22") (pin "2") (pinfunction "I1_2") (pintype "input"))
      (node (ref "E22") (pin "6") (pinfunction "I0_6") (pintype "input"))
    )
    (net (code "2") (name "+3VA") (class "Default")
      (node (ref "DC_ERASE") (pin "1") (pinfunction "O_1") (pintype "passive"))
      (node (ref "E7") (pin "2") (pinfunction "I1_2") (pintype "input"))
      (node (ref "R13") (pin "1") (pinfunction "1_1") (pintype "passive"))
      (node (ref "R15") (pin "2") (pinfunction "2_2") (pintype "passive"))
    )
    (net (code "3") (name "+3VB") (class "Default")
      (node (ref "E4") (pin "4") (pinfunction "I2_4") (pintype "input"))
      (node (ref "R12") (pin "1") (pinfunction "1_1") (pintype "passive"))
      (node (ref "R14") (pin "2") (pinfunction "2_2") (pintype "passive"))
    )
    (net (code "4") (name "+15V") (class "Default")
      (node (ref "C44") (pin "+") (pinfunction "+_+") (pintype "passive"))
      (node (ref "E25") (pin "7") (pinfunction "V+_7") (pintype "power_in"))
      (node (ref "POWER") (pin "3") (pinfunction "3_3") (pintype "passive"))
      (node (ref "R1") (pin "2") (pinfunction "2_2") (pintype "passive"))
      (node (ref "R2") (pin "2") (pinfunction "2_2") (pintype "passive"))
      (node (ref "R20") (pin "2") (pinfunction "2_2") (pintype "passive"))
      (node (ref "R21") (pin "2") (pinfunction "2_2") (pintype "passive"))
      (node (ref "R3") (pin "2") (pinfunction "2_2") (pintype "passive"))
    )
    (net (code "5") (name "-15V") (class "Default")
      (node (ref "C45") (pin "-") (pinfunction "-_-") (pintype "passive"))
      (node (ref "E25") (pin "4") (pinfunction "V-_4") (pintype "power_in"))
      (node (ref "POWER") (pin "4") (pinfunction "4_4") (pintype "passive"))
    )
    (net (code "6") (name "0BIT") (class "Default")
      (node (ref "E1") (pin "6") (pinfunction "O_6") (pintype "output"))
      (node (ref "E4") (pin "9") (pinfunction "I0_9") (pintype "input"))
    )
    (net (code "7") (name "1BIT") (class "Default")
      (node (ref "E1") (pin "8") (pinfunction "O_8") (pintype "output"))
      (node (ref "E4") (pin "10") (pinfunction "I1_10") (pintype "input"))
    )
    (net (code "8") (name "1L") (class "Default")
      (node (ref "E2") (pin "11") (pinfunction "CLK_11") (pintype "input"))
      (node (ref "E5") (pin "12") (pinfunction "D_12") (pintype "input"))
      (node (ref "E5") (pin "8") (pinfunction "~{Q}_8") (pintype "output"))
      (node (ref "E7") (pin "13") (pinfunction "I1_13") (pintype "input"))
    )
    (net (code "9") (name "2BIT") (class "Default")
      (node (ref "E1") (pin "12") (pinfunction "O_12") (pintype "output"))
      (node (ref "E4") (pin "12") (pinfunction "I2_12") (pintype "input"))
    )
    (net (code "10") (name "2H") (class "Default")
      (node (ref "E1") (pin "11") (pinfunction "I2_11") (pintype "input"))
      (node (ref "E2") (pin "9") (pinfunction "Q_9") (pintype "output"))
      (node (ref "E4") (pin "1") (pinfunction "I0_1") (pintype "input"))
    )
    (net (code "11") (name "2L") (class "Default")
      (node (ref "E1") (pin "2") (pinfunction "I1_2") (pintype "input"))
      (node (ref "E1") (pin "3") (pinfunction "I0_3") (pintype "input"))
      (node (ref "E2") (pin "12") (pinfunction "D_12") (pintype "input"))
      (node (ref "E2") (pin "3") (pinfunction "CLK_3") (pintype "input"))
      (node (ref "E2") (pin "8") (pinfunction "~{Q}_8") (pintype "output"))
    )
    (net (code "12") (name "3BIT") (class "Default")
      (node (ref "E4") (pin "13") (pinfunction "I3_13") (pintype "input"))
      (node (ref "E4") (pin "6") (pinfunction "O_6") (pintype "output"))
    )
    (net (code "13") (name "4H") (class "Default")
      (node (ref "E1") (pin "1") (pinfunction "I0_1") (pintype "input"))
      (node (ref "E2") (pin "5") (pinfunction "Q_5") (pintype "output"))
      (node (ref "E4") (pin "2") (pinfunction "I1_2") (pintype "input"))
    )
    (net (code "14") (name "4L") (class "Default")
      (node (ref "E1") (pin "10") (pinfunction "I1_10") (pintype "input"))
      (node (ref "E1") (pin "4") (pinfunction "I1_4") (pintype "input"))
      (node (ref "E2") (pin "2") (pinfunction "D_2") (pintype "input"))
      (node (ref "E2") (pin "6") (pinfunction "~{Q}_6") (pintype "output"))
    )
    (net (code "15") (name "202_DETECT_L") (class "Default")
      (node (ref "E23") (pin "11") (pinfunction "I2_11") (pintype "input"))
      (node (ref "E24") (pin "6") (pinfunction "O_6") (pintype "output"))
    )
    (net (code "16") (name "ADDRESS_INVALID_L") (class "Default")
      (node (ref "ADDR_INV") (pin "B") (pinfunction "B_B") (pintype "passive"))
      (node (ref "E21") (pin "5") (pinfunction "O_5") (pintype "open_collector"))
    )
    (net (code "17") (name "ADDR_COUNTER_1") (class "Default")
      (node (ref "E19") (pin "3") (pinfunction "QA_3") (pintype "output"))
      (node (ref "E26") (pin "5") (pinfunction "I1_5") (pintype "input"))
    )
    (net (code "18") (name "ADDR_COUNTER_2") (class "Default")
      (node (ref "E19") (pin "2") (pinfunction "QB_2") (pintype "output"))
      (node (ref "E24") (pin "1") (pinfunction "I0_1") (pintype "input"))
      (node (ref "E26") (pin "1") (pinfunction "I0_1") (pintype "input"))
    )
    (net (code "19") (name "ADDR_COUNTER_4") (class "Default")
      (node (ref "E19") (pin "6") (pinfunction "QC_6") (pintype "output"))
      (node (ref "E27") (pin "5") (pinfunction "I1_5") (pintype "input"))
    )
    (net (code "20") (name "ADDR_COUNTER_8") (class "Default")
      (node (ref "E19") (pin "7") (pinfunction "QD_7") (pintype "output"))
      (node (ref "E24") (pin "2") (pinfunction "I1_2") (pintype "input"))
      (node (ref "E27") (pin "1") (pinfunction "I0_1") (pintype "input"))
    )
    (net (code "21") (name "ADDR_COUNTER_16") (class "Default")
      (node (ref "E20") (pin "3") (pinfunction "QA_3") (pintype "output"))
      (node (ref "E28") (pin "5") (pinfunction "I1_5") (pintype "input"))
    )
    (net (code "22") (name "ADDR_COUNTER_32") (class "Default")
      (node (ref "E20") (pin "2") (pinfunction "QB_2") (pintype "output"))
      (node (ref "E23") (pin "3") (pinfunction "I0_3") (pintype "input"))
      (node (ref "E28") (pin "1") (pinfunction "I0_1") (pintype "input"))
    )
    (net (code "23") (name "ADDR_COUNTER_64") (class "Default")
      (node (ref "E20") (pin "6") (pinfunction "QC_6") (pintype "output"))
      (node (ref "E23") (pin "4") (pinfunction "I1_4") (pintype "input"))
      (node (ref "E24") (pin "4") (pinfunction "I2_4") (pintype "input"))
      (node (ref "E29") (pin "5") (pinfunction "I1_5") (pintype "input"))
    )
    (net (code "24") (name "ADDR_COUNTER_128") (class "Default")
      (node (ref "E20") (pin "7") (pinfunction "QD_7") (pintype "output"))
      (node (ref "E23") (pin "5") (pinfunction "I2_5") (pintype "input"))
      (node (ref "E24") (pin "5") (pinfunction "I3_5") (pintype "input"))
      (node (ref "E29") (pin "1") (pinfunction "I0_1") (pintype "input"))
    )
    (net (code "25") (name "ADDR_SOURCE_H") (class "Default")
      (node (ref "E18") (pin "5") (pinfunction "Q_5") (pintype "output"))
      (node (ref "E26") (pin "10") (pinfunction "I1_10") (pintype "input"))
      (node (ref "E26") (pin "13") (pinfunction "I1_13") (pintype "input"))
      (node (ref "E27") (pin "10") (pinfunction "I1_10") (pintype "input"))
      (node (ref "E27") (pin "13") (pinfunction "I1_13") (pintype "input"))
      (node (ref "E28") (pin "10") (pinfunction "I1_10") (pintype "input"))
      (node (ref "E28") (pin "13") (pinfunction "I1_13") (pintype "input"))
      (node (ref "E29") (pin "10") (pinfunction "I1_10") (pintype "input"))
      (node (ref "E29") (pin "13") (pinfunction "I1_13") (pintype "input"))
    )
    (net (code "26") (name "ADDR_SOURCE_L") (class "Default")
      (node (ref "E16") (pin "10") (pinfunction "I1_10") (pintype "input"))
      (node (ref "E16") (pin "4") (pinfunction "I1_4") (pintype "input"))
      (node (ref "E18") (pin "2") (pinfunction "D_2") (pintype "input"))
      (node (ref "E18") (pin "6") (pinfunction "~{Q}_6") (pintype "output"))
      (node (ref "E26") (pin "2") (pinfunction "I1_2") (pintype "input"))
      (node (ref "E26") (pin "4") (pinfunction "I0_4") (pintype "input"))
      (node (ref "E27") (pin "2") (pinfunction "I1_2") (pintype "input"))
      (node (ref "E27") (pin "4") (pinfunction "I0_4") (pintype "input"))
      (node (ref "E28") (pin "2") (pinfunction "I1_2") (pintype "input"))
      (node (ref "E28") (pin "4") (pinfunction "I0_4") (pintype "input"))
      (node (ref "E29") (pin "2") (pinfunction "I1_2") (pintype "input"))
      (node (ref "E29") (pin "4") (pinfunction "I0_4") (pintype "input"))
    )
    (net (code "27") (name "BIT_0L") (class "Default")
      (node (ref "BIT0") (pin "2") (pinfunction "P_2") (pintype "passive"))
      (node (ref "E1") (pin "5") (pinfunction "I2_5") (pintype "input"))
    )
    (net (code "28") (name "BIT_1L") (class "Default")
      (node (ref "BIT1") (pin "2") (pinfunction "P_2") (pintype "passive"))
      (node (ref "E1") (pin "9") (pinfunction "I0_9") (pintype "input"))
    )
    (net (code "29") (name "BIT_2L") (class "Default")
      (node (ref "BIT2") (pin "2") (pinfunction "P_2") (pintype "passive"))
      (node (ref "E1") (pin "13") (pinfunction "I2_13") (pintype "input"))
    )
    (net (code "30") (name "BIT_3L") (class "Default")
      (node (ref "BIT3") (pin "2") (pinfunction "P_2") (pintype "passive"))
      (node (ref "E4") (pin "5") (pinfunction "I3_5") (pintype "input"))
    )
    (net (code "31") (name "BUS_AC_LO_L") (class "Default")
      (node (ref "C39") (pin "1") (pinfunction "1_1") (pintype "passive"))
      (node (ref "J1") (pin "VV") (pinfunction "P$2_VV") (pintype "bidirectional"))
      (node (ref "R46") (pin "1") (pinfunction "1_1") (pintype "passive"))
    )
    (net (code "32") (name "BUS_ADDRESS_INVALID_L") (class "Default")
      (node (ref "E17") (pin "5") (pinfunction "I1_5") (pintype "input"))
      (node (ref "J2") (pin "C") (pinfunction "P$2_C") (pintype "bidirectional"))
      (node (ref "R26") (pin "1") (pinfunction "1_1") (pintype "passive"))
      (node (ref "RN3") (pin "3") (pinfunction "2_3") (pintype "passive"))
      (node (ref "RN7") (pin "3") (pinfunction "2_3") (pintype "passive"))
    )
    (net (code "33") (name "BUS_ADDR_ACCEPTED_L") (class "Default")
      (node (ref "J2") (pin "H") (pinfunction "P$2_H") (pintype "bidirectional"))
      (node (ref "RN3") (pin "5") (pinfunction "2_5") (pintype "passive"))
      (node (ref "RN7") (pin "5") (pinfunction "2_5") (pintype "passive"))
    )
    (net (code "34") (name "BUS_CA_00_L") (class "Default")
      (node (ref "E30") (pin "5") (pinfunction "O_5") (pintype "open_collector"))
      (node (ref "J2") (pin "Y") (pinfunction "P$2_Y") (pintype "bidirectional"))
      (node (ref "R147") (pin "1") (pinfunction "1_1") (pintype "passive"))
      (node (ref "R148") (pin "2") (pinfunction "2_2") (pintype "passive"))
    )
    (net (code "35") (name "BUS_CA_01_L") (class "Default")
      (node (ref "E30") (pin "3") (pinfunction "O_3") (pintype "open_collector"))
      (node (ref "J2") (pin "SS") (pinfunction "P$2_SS") (pintype "bidirectional"))
      (node (ref "RN4") (pin "3") (pinfunction "2_3") (pintype "passive"))
      (node (ref "RN8") (pin "3") (pinfunction "2_3") (pintype "passive"))
    )
    (net (code "36") (name "BUS_CA_02_L") (class "Default")
      (node (ref "E31") (pin "5") (pinfunction "O_5") (pintype "open_collector"))
      (node (ref "J2") (pin "U") (pinfunction "P$2_U") (pintype "bidirectional"))
      (node (ref "RN3") (pin "10") (pinfunction "2_10") (pintype "passive"))
      (node (ref "RN7") (pin "10") (pinfunction "2_10") (pintype "passive"))
    )
    (net (code "37") (name "BUS_CA_03_L") (class "Default")
      (node (ref "E31") (pin "3") (pinfunction "O_3") (pintype "open_collector"))
      (node (ref "J2") (pin "UU") (pinfunction "P$2_UU") (pintype "bidirectional"))
      (node (ref "RN4") (pin "2") (pinfunction "2_2") (pintype "passive"))
      (node (ref "RN8") (pin "2") (pinfunction "2_2") (pintype "passive"))
    )
    (net (code "38") (name "BUS_CA_04_L") (class "Default")
      (node (ref "E32") (pin "5") (pinfunction "O_5") (pintype "open_collector"))
      (node (ref "J2") (pin "MM") (pinfunction "P$2_MM") (pintype "bidirectional"))
      (node (ref "RN4") (pin "5") (pinfunction "2_5") (pintype "passive"))
      (node (ref "RN8") (pin "5") (pinfunction "2_5") (pintype "passive"))
    )
    (net (code "39") (name "BUS_CA_05_L") (class "Default")
      (node (ref "E32") (pin "3") (pinfunction "O_3") (pintype "open_collector"))
      (node (ref "J2") (pin "CC") (pinfunction "P$2_CC") (pintype "bidirectional"))
      (node (ref "RN4") (pin "9") (pinfunction "2_9") (pintype "passive"))
      (node (ref "RN8") (pin "9") (pinfunction "2_9") (pintype "passive"))
    )
    (net (code "40") (name "BUS_CA_06_L") (class "Default")
      (node (ref "E33") (pin "5") (pinfunction "O_5") (pintype "open_collector"))
      (node (ref "J2") (pin "PP") (pinfunction "P$2_PP") (pintype "bidirectional"))
      (node (ref "RN4") (pin "4") (pinfunction "2_4") (pintype "passive"))
      (node (ref "RN8") (pin "4") (pinfunction "2_4") (pintype "passive"))
    )
    (net (code "41") (name "BUS_CA_07_L") (class "Default")
      (node (ref "E33") (pin "3") (pinfunction "O_3") (pintype "open_collector"))
      (node (ref "J2") (pin "HH") (pinfunction "P$2_HH") (pintype "bidirectional"))
      (node (ref "RN4") (pin "7") (pinfunction "2_7") (pintype "passive"))
      (node (ref "RN8") (pin "7") (pinfunction "2_7") (pintype "passive"))
    )
    (net (code "42") (name "BUS_DATA&CLOCK_L") (class "Default")
      (node (ref "E34") (pin "3") (pinfunction "O_3") (pintype "open_collector"))
      (node (ref "J2") (pin "KK") (pinfunction "P$2_KK") (pintype "bidirectional"))
      (node (ref "RN4") (pin "6") (pinfunction "2_6") (pintype "passive"))
      (node (ref "RN8") (pin "6") (pinfunction "2_6") (pintype "passive"))
    )
    (net (code "43") (name "BUS_DC_LO_L") (class "Default")
      (node (ref "C53") (pin "1") (pinfunction "1_1") (pintype "passive"))
      (node (ref "J1") (pin "TT") (pinfunction "P$2_TT") (pintype "bidirectional"))
      (node (ref "R50") (pin "1") (pinfunction "1_1") (pintype "passive"))
    )
    (net (code "44") (name "BUS_FILE_READY") (class "Default")
      (node (ref "J1") (pin "V") (pinfunction "P$2_V") (pintype "bidirectional"))
      (node (ref "RN1") (pin "9") (pinfunction "2_9") (pintype "passive"))
      (node (ref "RN5") (pin "9") (pinfunction "2_9") (pintype "passive"))
    )
    (net (code "45") (name "BUS_HIGH_DENSITY_L") (class "Default")
      (node (ref "J1") (pin "N") (pinfunction "P$2_N") (pintype "bidirectional"))
      (node (ref "RN1") (pin "6") (pinfunction "2_6") (pintype "passive"))
      (node (ref "RN5") (pin "6") (pinfunction "2_6") (pintype "passive"))
    )
    (net (code "46") (name "BUS_INDEX_L") (class "Default")
      (node (ref "E11") (pin "1") (pinfunction "CLR_1") (pintype "input"))
      (node (ref "E11") (pin "11") (pinfunction "CLK_11") (pintype "input"))
      (node (ref "J1") (pin "Z") (pinfunction "P$2_Z") (pintype "bidirectional"))
      (node (ref "RN2") (pin "10") (pinfunction "2_10") (pintype "passive"))
      (node (ref "RN6") (pin "10") (pinfunction "2_10") (pintype "passive"))
    )
    (net (code "47") (name "BUS_READ_GATE_L") (class "Default")
      (node (ref "J1") (pin "L") (pinfunction "P$2_L") (pintype "bidirectional"))
      (node (ref "RN1") (pin "5") (pinfunction "2_5") (pintype "passive"))
      (node (ref "RN5") (pin "5") (pinfunction "2_5") (pintype "passive"))
    )
    (net (code "48") (name "BUS_RESTORE_L") (class "Default")
      (node (ref "C34") (pin "1") (pinfunction "1_1") (pintype "passive"))
      (node (ref "E22") (pin "5") (pinfunction "O_5") (pintype "open_collector"))
      (node (ref "J2") (pin "P") (pinfunction "P$2_P") (pintype "bidirectional"))
      (node (ref "RN3") (pin "8") (pinfunction "2_8") (pintype "passive"))
      (node (ref "RN7") (pin "8") (pinfunction "2_8") (pintype "passive"))
    )
    (net (code "49") (name "BUS_RWS_READY_L") (class "Default")
      (node (ref "E12") (pin "5") (pinfunction "I_5") (pintype "input"))
      (node (ref "J2") (pin "EE") (pinfunction "P$2_EE") (pintype "bidirectional"))
      (node (ref "RN4") (pin "8") (pinfunction "2_8") (pintype "passive"))
      (node (ref "RN8") (pin "8") (pinfunction "2_8") (pintype "passive"))
    )
    (net (code "50") (name "BUS_SECTOR_ADDR_0L") (class "Default")
      (node (ref "E6") (pin "5") (pinfunction "I_5") (pintype "input"))
      (node (ref "J1") (pin "DD") (pinfunction "P$2_DD") (pintype "bidirectional"))
      (node (ref "R17") (pin "1") (pinfunction "1_1") (pintype "passive"))
      (node (ref "RN2") (pin "8") (pinfunction "2_8") (pintype "passive"))
      (node (ref "RN6") (pin "8") (pinfunction "2_8") (pintype "passive"))
    )
    (net (code "51") (name "BUS_SECTOR_ADDR_1L") (class "Default")
      (node (ref "E6") (pin "13") (pinfunction "I_13") (pintype "input"))
      (node (ref "J2") (pin "K") (pinfunction "P$2_K") (pintype "bidirectional"))
      (node (ref "R18") (pin "1") (pinfunction "1_1") (pintype "passive"))
      (node (ref "RN3") (pin "6") (pinfunction "2_6") (pintype "passive"))
      (node (ref "RN7") (pin "6") (pinfunction "2_6") (pintype "passive"))
    )
    (net (code "52") (name "BUS_SECTOR_ADDR_2L") (class "Default")
      (node (ref "E6") (pin "11") (pinfunction "I_11") (pintype "input"))
      (node (ref "J1") (pin "FF") (pinfunction "P$2_FF") (pintype "bidirectional"))
      (node (ref "R16") (pin "1") (pinfunction "1_1") (pintype "passive"))
      (node (ref "RN2") (pin "7") (pinfunction "2_7") (pintype "passive"))
      (node (ref "RN6") (pin "7") (pinfunction "2_7") (pintype "passive"))
    )
    (net (code "53") (name "BUS_SECTOR_ADDR_3L") (class "Default")
      (node (ref "E6") (pin "9") (pinfunction "I_9") (pintype "input"))
      (node (ref "J1") (pin "LL") (pinfunction "P$2_LL") (pintype "bidirectional"))
      (node (ref "R11") (pin "1") (pinfunction "1_1") (pintype "passive"))
      (node (ref "RN2") (pin "5") (pinfunction "2_5") (pintype "passive"))
      (node (ref "RN6") (pin "5") (pinfunction "2_5") (pintype "passive"))
    )
    (net (code "54") (name "BUS_SECTOR_PULSE_L") (class "Default")
      (node (ref "J1") (pin "T") (pinfunction "P$2_T") (pintype "bidirectional"))
      (node (ref "RN1") (pin "8") (pinfunction "2_8") (pintype "passive"))
      (node (ref "RN5") (pin "8") (pinfunction "2_8") (pintype "passive"))
    )
    (net (code "55") (name "BUS_SEEK_INCOMPLETE_L") (class "Default")
      (node (ref "E21") (pin "7") (pinfunction "I1_7") (pintype "input"))
      (node (ref "J2") (pin "E") (pinfunction "P$2_E") (pintype "bidirectional"))
      (node (ref "R27") (pin "1") (pinfunction "1_1") (pintype "passive"))
      (node (ref "RN3") (pin "4") (pinfunction "2_4") (pintype "passive"))
      (node (ref "RN7") (pin "4") (pinfunction "2_4") (pintype "passive"))
    )
    (net (code "56") (name "BUS_STROBE_L") (class "Default")
      (node (ref "E22") (pin "3") (pinfunction "O_3") (pintype "open_collector"))
      (node (ref "J1") (pin "RR") (pinfunction "P$2_RR") (pintype "bidirectional"))
      (node (ref "RN2") (pin "3") (pinfunction "2_3") (pintype "passive"))
      (node (ref "RN6") (pin "3") (pinfunction "2_3") (pintype "passive"))
    )
    (net (code "57") (name "BUS_WP_SET_L") (class "Default")
      (node (ref "J1") (pin "J") (pinfunction "P$2_J") (pintype "bidirectional"))
      (node (ref "RN1") (pin "4") (pinfunction "2_4") (pintype "passive"))
      (node (ref "RN5") (pin "4") (pinfunction "2_4") (pintype "passive"))
    )
    (net (code "58") (name "BUS_WP_STATUS_L") (class "Default")
      (node (ref "J1") (pin "R") (pinfunction "P$2_R") (pintype "bidirectional"))
      (node (ref "RN1") (pin "7") (pinfunction "2_7") (pintype "passive"))
      (node (ref "RN5") (pin "7") (pinfunction "2_7") (pintype "passive"))
    )
    (net (code "59") (name "BUS_WRITE_CK") (class "Default")
      (node (ref "J1") (pin "JJ") (pinfunction "P$2_JJ") (pintype "bidirectional"))
      (node (ref "RN2") (pin "6") (pinfunction "2_6") (pintype "passive"))
      (node (ref "RN6") (pin "6") (pinfunction "2_6") (pintype "passive"))
    )
    (net (code "60") (name "BUS_WRITE_GATE_L") (class "Default")
      (node (ref "E34") (pin "5") (pinfunction "O_5") (pintype "open_collector"))
      (node (ref "J1") (pin "BB") (pinfunction "P$2_BB") (pintype "bidirectional"))
      (node (ref "RN2") (pin "9") (pinfunction "2_9") (pintype "passive"))
      (node (ref "RN6") (pin "9") (pinfunction "2_9") (pintype "passive"))
    )
    (net (code "61") (name "CA_SW_1") (class "Default")
      (node (ref "CYL1") (pin "3") (pinfunction "S_3") (pintype "passive"))
      (node (ref "E26") (pin "9") (pinfunction "I0_9") (pintype "input"))
      (node (ref "R45") (pin "2") (pinfunction "2_2") (pintype "passive"))
    )
    (net (code "62") (name "CA_SW_2") (class "Default")
      (node (ref "CYL2") (pin "3") (pinfunction "S_3") (pintype "passive"))
      (node (ref "E26") (pin "12") (pinfunction "I0_12") (pintype "input"))
      (node (ref "R44") (pin "2") (pinfunction "2_2") (pintype "passive"))
    )
    (net (code "63") (name "CA_SW_4") (class "Default")
      (node (ref "CYL4") (pin "3") (pinfunction "S_3") (pintype "passive"))
      (node (ref "E27") (pin "9") (pinfunction "I0_9") (pintype "input"))
      (node (ref "R43") (pin "2") (pinfunction "2_2") (pintype "passive"))
    )
    (net (code "64") (name "CA_SW_8") (class "Default")
      (node (ref "CYL8") (pin "3") (pinfunction "S_3") (pintype "passive"))
      (node (ref "E27") (pin "12") (pinfunction "I0_12") (pintype "input"))
      (node (ref "R42") (pin "2") (pinfunction "2_2") (pintype "passive"))
    )
    (net (code "65") (name "CA_SW_16") (class "Default")
      (node (ref "CYL16") (pin "3") (pinfunction "S_3") (pintype "passive"))
      (node (ref "E28") (pin "9") (pinfunction "I0_9") (pintype "input"))
      (node (ref "R41") (pin "2") (pinfunction "2_2") (pintype "passive"))
    )
    (net (code "66") (name "CA_SW_32") (class "Default")
      (node (ref "CYL32") (pin "3") (pinfunction "S_3") (pintype "passive"))
      (node (ref "E28") (pin "12") (pinfunction "I0_12") (pintype "input"))
      (node (ref "R40") (pin "2") (pinfunction "2_2") (pintype "passive"))
    )
    (net (code "67") (name "CA_SW_64") (class "Default")
      (node (ref "CYL64") (pin "3") (pinfunction "S_3") (pintype "passive"))
      (node (ref "E29") (pin "9") (pinfunction "I0_9") (pintype "input"))
      (node (ref "R39") (pin "2") (pinfunction "2_2") (pintype "passive"))
    )
    (net (code "68") (name "CA_SW_128") (class "Default")
      (node (ref "CYL128") (pin "3") (pinfunction "S_3") (pintype "passive"))
      (node (ref "E29") (pin "12") (pinfunction "I0_12") (pintype "input"))
      (node (ref "R38") (pin "2") (pinfunction "2_2") (pintype "passive"))
    )
    (net (code "69") (name "CLOCK_H") (class "Default")
      (node (ref "E7") (pin "10") (pinfunction "I1_10") (pintype "input"))
      (node (ref "E7") (pin "12") (pinfunction "I0_12") (pintype "input"))
      (node (ref "E8") (pin "1") (pinfunction "A_1") (pintype "input"))
      (node (ref "E8") (pin "5") (pinfunction "Q_5") (pintype "output"))
    )
    (net (code "70") (name "CONSTANT_WRITE_L") (class "Default")
      (node (ref "CW") (pin "2") (pinfunction "P_2") (pintype "passive"))
      (node (ref "E11") (pin "4") (pinfunction "PRE_4") (pintype "input"))
    )
    (net (code "71") (name "DC_ERASE") (class "Default")
      (node (ref "DC_ERASE") (pin "2") (pinfunction "P_2") (pintype "passive"))
      (node (ref "E10") (pin "9") (pinfunction "I0_9") (pintype "input"))
    )
    (net (code "72") (name "FWD_L") (class "Default")
      (node (ref "E16") (pin "9") (pinfunction "I0_9") (pintype "input"))
      (node (ref "E17") (pin "9") (pinfunction "I0_9") (pintype "input"))
      (node (ref "FWD/REV") (pin "3") (pinfunction "S_3") (pintype "passive"))
      (node (ref "R36") (pin "1") (pinfunction "1_1") (pintype "passive"))
    )
    (net (code "73") (name "GND") (class "Default")
      (node (ref "BIT0") (pin "1") (pinfunction "O_1") (pintype "passive"))
      (node (ref "BIT1") (pin "1") (pinfunction "O_1") (pintype "passive"))
      (node (ref "BIT2") (pin "1") (pinfunction "O_1") (pintype "passive"))
      (node (ref "BIT3") (pin "1") (pinfunction "O_1") (pintype "passive"))
      (node (ref "C1") (pin "2") (pinfunction "2_2") (pintype "passive"))
      (node (ref "C10") (pin "2") (pinfunction "2_2") (pintype "passive"))
      (node (ref "C11") (pin "2") (pinfunction "2_2") (pintype "passive"))
      (node (ref "C12") (pin "2") (pinfunction "2_2") (pintype "passive"))
      (node (ref "C13") (pin "2") (pinfunction "2_2") (pintype "passive"))
      (node (ref "C14") (pin "2") (pinfunction "2_2") (pintype "passive"))
      (node (ref "C15") (pin "2") (pinfunction "2_2") (pintype "passive"))
      (node (ref "C16") (pin "2") (pinfunction "2_2") (pintype "passive"))
      (node (ref "C17") (pin "2") (pinfunction "2_2") (pintype "passive"))
      (node (ref "C18") (pin "2") (pinfunction "2_2") (pintype "passive"))
      (node (ref "C19") (pin "2") (pinfunction "2_2") (pintype "passive"))
      (node (ref "C2") (pin "2") (pinfunction "2_2") (pintype "passive"))
      (node (ref "C20") (pin "2") (pinfunction "2_2") (pintype "passive"))
      (node (ref "C21") (pin "2") (pinfunction "2_2") (pintype "passive"))
      (node (ref "C22") (pin "2") (pinfunction "2_2") (pintype "passive"))
      (node (ref "C23") (pin "2") (pinfunction "2_2") (pintype "passive"))
      (node (ref "C24") (pin "2") (pinfunction "2_2") (pintype "passive"))
      (node (ref "C26") (pin "2") (pinfunction "2_2") (pintype "passive"))
      (node (ref "C27") (pin "2") (pinfunction "2_2") (pintype "passive"))
      (node (ref "C28") (pin "2") (pinfunction "2_2") (pintype "passive"))
      (node (ref "C29") (pin "2") (pinfunction "2_2") (pintype "passive"))
      (node (ref "C3") (pin "2") (pinfunction "2_2") (pintype "passive"))
      (node (ref "C30") (pin "2") (pinfunction "2_2") (pintype "passive"))
      (node (ref "C31") (pin "2") (pinfunction "2_2") (pintype "passive"))
      (node (ref "C32") (pin "2") (pinfunction "2_2") (pintype "passive"))
      (node (ref "C33") (pin "2") (pinfunction "2_2") (pintype "passive"))
      (node (ref "C34") (pin "2") (pinfunction "2_2") (pintype "passive"))
      (node (ref "C36") (pin "2") (pinfunction "2_2") (pintype "passive"))
      (node (ref "C38") (pin "2") (pinfunction "2_2") (pintype "passive"))
      (node (ref "C39") (pin "2") (pinfunction "2_2") (pintype "passive"))
      (node (ref "C4") (pin "2") (pinfunction "2_2") (pintype "passive"))
      (node (ref "C40") (pin "2") (pinfunction "2_2") (pintype "passive"))
      (node (ref "C41") (pin "2") (pinfunction "2_2") (pintype "passive"))
      (node (ref "C42") (pin "2") (pinfunction "2_2") (pintype "passive"))
      (node (ref "C43") (pin "2") (pinfunction "2_2") (pintype "passive"))
      (node (ref "C44") (pin "-") (pinfunction "-_-") (pintype "passive"))
      (node (ref "C45") (pin "+") (pinfunction "+_+") (pintype "passive"))
      (node (ref "C5") (pin "2") (pinfunction "2_2") (pintype "passive"))
      (node (ref "C52") (pin "-") (pinfunction "-_-") (pintype "passive"))
      (node (ref "C53") (pin "2") (pinfunction "2_2") (pintype "passive"))
      (node (ref "C6") (pin "2") (pinfunction "2_2") (pintype "passive"))
      (node (ref "C60") (pin "-") (pinfunction "-_-") (pintype "passive"))
      (node (ref "C61") (pin "-") (pinfunction "-_-") (pintype "passive"))
      (node (ref "C67") (pin "-") (pinfunction "-_-") (pintype "passive"))
      (node (ref "C68") (pin "-") (pinfunction "-_-") (pintype "passive"))
      (node (ref "C7") (pin "2") (pinfunction "2_2") (pintype "passive"))
      (node (ref "C8") (pin "2") (pinfunction "2_2") (pintype "passive"))
      (node (ref "C9") (pin "2") (pinfunction "2_2") (pintype "passive"))
      (node (ref "CW") (pin "3") (pinfunction "S_3") (pintype "passive"))
      (node (ref "CYL1") (pin "2") (pinfunction "P_2") (pintype "passive"))
      (node (ref "CYL128") (pin "2") (pinfunction "P_2") (pintype "passive"))
      (node (ref "CYL16") (pin "2") (pinfunction "P_2") (pintype "passive"))
      (node (ref "CYL2") (pin "2") (pinfunction "P_2") (pintype "passive"))
      (node (ref "CYL32") (pin "2") (pinfunction "P_2") (pintype "passive"))
      (node (ref "CYL4") (pin "2") (pinfunction "P_2") (pintype "passive"))
      (node (ref "CYL64") (pin "2") (pinfunction "P_2") (pintype "passive"))
      (node (ref "CYL8") (pin "2") (pinfunction "P_2") (pintype "passive"))
      (node (ref "D5") (pin "A") (pinfunction "A_A") (pintype "passive"))
      (node (ref "DC_ERASE") (pin "3") (pinfunction "S_3") (pintype "passive"))
      (node (ref "DRIVE") (pin "A") (pinfunction "A_A") (pintype "passive"))
      (node (ref "E12") (pin "9") (pinfunction "I_9") (pintype "input"))
      (node (ref "E14") (pin "1") (pinfunction "A_1") (pintype "input"))
      (node (ref "E14") (pin "9") (pinfunction "A_9") (pintype "input"))
      (node (ref "E15") (pin "10") (pinfunction "I1_10") (pintype "input"))
      (node (ref "E15") (pin "12") (pinfunction "I0_12") (pintype "input"))
      (node (ref "E15") (pin "13") (pinfunction "I1_13") (pintype "input"))
      (node (ref "E15") (pin "4") (pinfunction "I0_4") (pintype "input"))
      (node (ref "E15") (pin "5") (pinfunction "I1_5") (pintype "input"))
      (node (ref "E15") (pin "9") (pinfunction "I0_9") (pintype "input"))
      (node (ref "E19") (pin "10") (pinfunction "C_10") (pintype "input"))
      (node (ref "E19") (pin "15") (pinfunction "A_15") (pintype "input"))
      (node (ref "E20") (pin "1") (pinfunction "B_1") (pintype "input"))
      (node (ref "E20") (pin "15") (pinfunction "A_15") (pintype "input"))
      (node (ref "E24") (pin "10") (pinfunction "I1_10") (pintype "input"))
      (node (ref "E24") (pin "12") (pinfunction "I2_12") (pintype "input"))
      (node (ref "E24") (pin "13") (pinfunction "I3_13") (pintype "input"))
      (node (ref "E24") (pin "9") (pinfunction "I0_9") (pintype "input"))
      (node (ref "E6") (pin "1") (pinfunction "I_1") (pintype "input"))
      (node (ref "E8") (pin "9") (pinfunction "A_9") (pintype "input"))
      (node (ref "FUNCTION") (pin "A") (pinfunction "A_A") (pintype "passive"))
      (node (ref "FWD/REV") (pin "2") (pinfunction "P_2") (pintype "passive"))
      (node (ref "HEAD") (pin "3") (pinfunction "S_3") (pintype "passive"))
      (node (ref "J1") (pin "A") (pinfunction "P$2_A") (pintype "bidirectional"))
      (node (ref "J1") (pin "AA") (pinfunction "P$2_AA") (pintype "bidirectional"))
      (node (ref "J1") (pin "B") (pinfunction "P$2_B") (pintype "bidirectional"))
      (node (ref "J1") (pin "C") (pinfunction "P$2_C") (pintype "bidirectional"))
      (node (ref "J1") (pin "CC") (pinfunction "P$2_CC") (pintype "bidirectional"))
      (node (ref "J1") (pin "E") (pinfunction "P$2_E") (pintype "bidirectional"))
      (node (ref "J1") (pin "EE") (pinfunction "P$2_EE") (pintype "bidirectional"))
      (node (ref "J1") (pin "H") (pinfunction "P$2_H") (pintype "bidirectional"))
      (node (ref "J1") (pin "HH") (pinfunction "P$2_HH") (pintype "bidirectional"))
      (node (ref "J1") (pin "K") (pinfunction "P$2_K") (pintype "bidirectional"))
      (node (ref "J1") (pin "KK") (pinfunction "P$2_KK") (pintype "bidirectional"))
      (node (ref "J1") (pin "M") (pinfunction "P$2_M") (pintype "bidirectional"))
      (node (ref "J1") (pin "MM") (pinfunction "P$2_MM") (pintype "bidirectional"))
      (node (ref "J1") (pin "P") (pinfunction "P$2_P") (pintype "bidirectional"))
      (node (ref "J1") (pin "PP") (pinfunction "P$2_PP") (pintype "bidirectional"))
      (node (ref "J1") (pin "S") (pinfunction "P$2_S") (pintype "bidirectional"))
      (node (ref "J1") (pin "SS") (pinfunction "P$2_SS") (pintype "bidirectional"))
      (node (ref "J1") (pin "U") (pinfunction "P$2_U") (pintype "bidirectional"))
      (node (ref "J1") (pin "UU") (pinfunction "P$2_UU") (pintype "bidirectional"))
      (node (ref "J1") (pin "W") (pinfunction "P$2_W") (pintype "bidirectional"))
      (node (ref "J1") (pin "Y") (pinfunction "P$2_Y") (pintype "bidirectional"))
      (node (ref "J2") (pin "B") (pinfunction "P$2_B") (pintype "bidirectional"))
      (node (ref "J2") (pin "BB") (pinfunction "P$2_BB") (pintype "bidirectional"))
      (node (ref "J2") (pin "D") (pinfunction "P$2_D") (pintype "bidirectional"))
      (node (ref "J2") (pin "DD") (pinfunction "P$2_DD") (pintype "bidirectional"))
      (node (ref "J2") (pin "F") (pinfunction "P$2_F") (pintype "bidirectional"))
      (node (ref "J2") (pin "FF") (pinfunction "P$2_FF") (pintype "bidirectional"))
      (node (ref "J2") (pin "J") (pinfunction "P$2_J") (pintype "bidirectional"))
      (node (ref "J2") (pin "JJ") (pinfunction "P$2_JJ") (pintype "bidirectional"))
      (node (ref "J2") (pin "L") (pinfunction "P$2_L") (pintype "bidirectional"))
      (node (ref "J2") (pin "LL") (pinfunction "P$2_LL") (pintype "bidirectional"))
      (node (ref "J2") (pin "N") (pinfunction "P$2_N") (pintype "bidirectional"))
      (node (ref "J2") (pin "NN") (pinfunction "P$2_NN") (pintype "bidirectional"))
      (node (ref "J2") (pin "R") (pinfunction "P$2_R") (pintype "bidirectional"))
      (node (ref "J2") (pin "RR") (pinfunction "P$2_RR") (pintype "bidirectional"))
      (node (ref "J2") (pin "T") (pinfunction "P$2_T") (pintype "bidirectional"))
      (node (ref "J2") (pin "TT") (pinfunction "P$2_TT") (pintype "bidirectional"))
      (node (ref "J2") (pin "V") (pinfunction "P$2_V") (pintype "bidirectional"))
      (node (ref "J2") (pin "VV") (pinfunction "P$2_VV") (pintype "bidirectional"))
      (node (ref "J2") (pin "X") (pinfunction "P$2_X") (pintype "bidirectional"))
      (node (ref "J2") (pin "Z") (pinfunction "P$2_Z") (pintype "bidirectional"))
      (node (ref "POWER") (pin "1") (pinfunction "1_1") (pintype "passive"))
      (node (ref "POWER_ON") (pin "B") (pinfunction "B_B") (pintype "passive"))
      (node (ref "R14") (pin "1") (pinfunction "1_1") (pintype "passive"))
      (node (ref "R148") (pin "1") (pinfunction "1_1") (pintype "passive"))
      (node (ref "R15") (pin "1") (pinfunction "1_1") (pintype "passive"))
      (node (ref "R23") (pin "1") (pinfunction "1_1") (pintype "passive"))
      (node (ref "R31") (pin "1") (pinfunction "1_1") (pintype "passive"))
      (node (ref "R70") (pin "1") (pinfunction "1_1") (pintype "passive"))
      (node (ref "RN5") (pin "1") (pinfunction "1_1") (pintype "passive"))
      (node (ref "RN6") (pin "1") (pinfunction "1_1") (pintype "passive"))
      (node (ref "RN6") (pin "2") (pinfunction "2_2") (pintype "passive"))
      (node (ref "RN7") (pin "1") (pinfunction "1_1") (pintype "passive"))
      (node (ref "RN8") (pin "1") (pinfunction "1_1") (pintype "passive"))
      (node (ref "RTZ") (pin "2") (pinfunction "P_2") (pintype "passive"))
      (node (ref "SECTOR") (pin "11") (pinfunction "11_11") (pintype "passive"))
      (node (ref "SECTOR") (pin "12") (pinfunction "12_12") (pintype "passive"))
      (node (ref "WRITE") (pin "2") (pinfunction "P_2") (pintype "passive"))
    )
    (net (code "74") (name "HEAD_SELECT_L") (class "Default")
      (node (ref "HEAD") (pin "2") (pinfunction "P_2") (pintype "passive"))
      (node (ref "J1") (pin "X") (pinfunction "P$2_X") (pintype "bidirectional"))
      (node (ref "RN1") (pin "10") (pinfunction "2_10") (pintype "passive"))
      (node (ref "RN5") (pin "10") (pinfunction "2_10") (pintype "passive"))
    )
    (net (code "75") (name "NEG1_DETECT_L") (class "Default")
      (node (ref "E23") (pin "10") (pinfunction "I1_10") (pintype "input"))
      (node (ref "E23") (pin "6") (pinfunction "O_6") (pintype "output"))
    )
    (net (code "76") (name "Net-(ADDR_INV-PadA)") (class "Default")
      (node (ref "ADDR_INV") (pin "A") (pinfunction "A_A") (pintype "passive"))
      (node (ref "R1") (pin "1") (pinfunction "1_1") (pintype "passive"))
    )
    (net (code "77") (name "Net-(BIT0A-S)") (class "Default")
      (node (ref "BIT0") (pin "3") (pinfunction "S_3") (pintype "passive"))
      (node (ref "BIT1") (pin "3") (pinfunction "S_3") (pintype "passive"))
      (node (ref "BIT2") (pin "3") (pinfunction "S_3") (pintype "passive"))
      (node (ref "BIT3") (pin "3") (pinfunction "S_3") (pintype "passive"))
      (node (ref "R7") (pin "1") (pinfunction "1_1") (pintype "passive"))
    )
    (net (code "78") (name "Net-(CWA-O)") (class "Default")
      (node (ref "CW") (pin "1") (pinfunction "O_1") (pintype "passive"))
      (node (ref "E11") (pin "10") (pinfunction "PRE_10") (pintype "input"))
      (node (ref "E11") (pin "2") (pinfunction "D_2") (pintype "input"))
      (node (ref "R4") (pin "1") (pinfunction "1_1") (pintype "passive"))
    )
    (net (code "79") (name "Net-(D2-PadC)") (class "Default")
      (node (ref "D2") (pin "C") (pinfunction "C_C") (pintype "passive"))
      (node (ref "D3") (pin "A") (pinfunction "A_A") (pintype "passive"))
    )
    (net (code "80") (name "Net-(D3-PadC)") (class "Default")
      (node (ref "D3") (pin "C") (pinfunction "C_C") (pintype "passive"))
      (node (ref "D4") (pin "A") (pinfunction "A_A") (pintype "passive"))
    )
    (net (code "81") (name "Net-(E2A-PRE)") (class "Default")
      (node (ref "E2") (pin "10") (pinfunction "PRE_10") (pintype "input"))
      (node (ref "E2") (pin "4") (pinfunction "PRE_4") (pintype "input"))
      (node (ref "E5") (pin "10") (pinfunction "PRE_10") (pintype "input"))
      (node (ref "R10") (pin "1") (pinfunction "1_1") (pintype "passive"))
    )
    (net (code "82") (name "Net-(E3A-A)") (class "Default")
      (node (ref "E3") (pin "15") (pinfunction "A_15") (pintype "input"))
      (node (ref "E6") (pin "6") (pinfunction "O_6") (pintype "output"))
    )
    (net (code "83") (name "Net-(E3A-B)") (class "Default")
      (node (ref "E3") (pin "14") (pinfunction "B_14") (pintype "input"))
      (node (ref "E6") (pin "12") (pinfunction "O_12") (pintype "output"))
    )
    (net (code "84") (name "Net-(E3A-C)") (class "Default")
      (node (ref "E3") (pin "13") (pinfunction "C_13") (pintype "input"))
      (node (ref "E6") (pin "10") (pinfunction "O_10") (pintype "output"))
    )
    (net (code "85") (name "Net-(E3A-D)") (class "Default")
      (node (ref "E3") (pin "12") (pinfunction "D_12") (pintype "input"))
      (node (ref "E6") (pin "8") (pinfunction "O_8") (pintype "output"))
    )
    (net (code "86") (name "Net-(E4B-O)") (class "Default")
      (node (ref "E4") (pin "8") (pinfunction "O_8") (pintype "output"))
      (node (ref "E7") (pin "9") (pinfunction "I0_9") (pintype "input"))
    )
    (net (code "87") (name "Net-(E5A-CLK)") (class "Default")
      (node (ref "E5") (pin "2") (pinfunction "D_2") (pintype "input"))
      (node (ref "E5") (pin "3") (pinfunction "CLK_3") (pintype "input"))
      (node (ref "E6") (pin "4") (pinfunction "O_4") (pintype "output"))
    )
    (net (code "88") (name "Net-(E5B-CLK)") (class "Default")
      (node (ref "E5") (pin "11") (pinfunction "CLK_11") (pintype "input"))
      (node (ref "E8") (pin "12") (pinfunction "~{Q}_12") (pintype "output"))
    )
    (net (code "89") (name "Net-(E6A-O)") (class "Default")
      (node (ref "E6") (pin "2") (pinfunction "O_2") (pintype "output"))
      (node (ref "E6") (pin "3") (pinfunction "I_3") (pintype "input"))
    )
    (net (code "90") (name "Net-(E7B-I0)") (class "Default")
      (node (ref "E7") (pin "11") (pinfunction "O_11") (pintype "output"))
      (node (ref "E7") (pin "4") (pinfunction "I0_4") (pintype "input"))
    )
    (net (code "91") (name "Net-(E7B-I1)") (class "Default")
      (node (ref "E7") (pin "5") (pinfunction "I1_5") (pintype "input"))
      (node (ref "E7") (pin "8") (pinfunction "O_8") (pintype "output"))
    )
    (net (code "92") (name "Net-(E8A-C)") (class "Default")
      (node (ref "C63") (pin "2") (pinfunction "2_2") (pintype "passive"))
      (node (ref "E8") (pin "14") (pinfunction "C_14") (pintype "input"))
    )
    (net (code "93") (name "Net-(E8A-R{slash}C)") (class "Default")
      (node (ref "C63") (pin "1") (pinfunction "1_1") (pintype "passive"))
      (node (ref "E8") (pin "15") (pinfunction "R/C_15") (pintype "input"))
      (node (ref "R9") (pin "E") (pinfunction "E_E") (pintype "passive"))
      (node (ref "R9") (pin "S") (pinfunction "S_S") (pintype "passive"))
    )
    (net (code "94") (name "Net-(E8A-~{Q})") (class "Default")
      (node (ref "E8") (pin "10") (pinfunction "B_10") (pintype "input"))
      (node (ref "E8") (pin "4") (pinfunction "~{Q}_4") (pintype "output"))
    )
    (net (code "95") (name "Net-(E8B-C)") (class "Default")
      (node (ref "C62") (pin "2") (pinfunction "2_2") (pintype "passive"))
      (node (ref "E8") (pin "6") (pinfunction "C_6") (pintype "input"))
    )
    (net (code "96") (name "Net-(E8B-R{slash}C)") (class "Default")
      (node (ref "C62") (pin "1") (pinfunction "1_1") (pintype "passive"))
      (node (ref "E8") (pin "7") (pinfunction "R/C_7") (pintype "input"))
      (node (ref "R8") (pin "1") (pinfunction "1_1") (pintype "passive"))
    )
    (net (code "97") (name "Net-(E10A-I1)") (class "Default")
      (node (ref "E10") (pin "2") (pinfunction "I1_2") (pintype "input"))
      (node (ref "E10") (pin "6") (pinfunction "O_6") (pintype "output"))
    )
    (net (code "98") (name "Net-(E10A-O)") (class "Default")
      (node (ref "E10") (pin "3") (pinfunction "O_3") (pintype "output"))
      (node (ref "E10") (pin "5") (pinfunction "I1_5") (pintype "input"))
      (node (ref "E11") (pin "12") (pinfunction "D_12") (pintype "input"))
      (node (ref "E11") (pin "13") (pinfunction "CLR_13") (pintype "input"))
    )
    (net (code "99") (name "Net-(E10C-I1)") (class "Default")
      (node (ref "E10") (pin "10") (pinfunction "I1_10") (pintype "input"))
      (node (ref "E7") (pin "6") (pinfunction "O_6") (pintype "output"))
    )
    (net (code "100") (name "Net-(E10C-O)") (class "Default")
      (node (ref "E10") (pin "8") (pinfunction "O_8") (pintype "output"))
      (node (ref "E34") (pin "1") (pinfunction "I0_1") (pintype "input"))
      (node (ref "E34") (pin "2") (pinfunction "I1_2") (pintype "input"))
    )
    (net (code "101") (name "Net-(E10D-I1)") (class "Default")
      (node (ref "E10") (pin "13") (pinfunction "I1_13") (pintype "input"))
      (node (ref "E7") (pin "3") (pinfunction "O_3") (pintype "output"))
    )
    (net (code "102") (name "Net-(E10D-O)") (class "Default")
      (node (ref "E10") (pin "11") (pinfunction "O_11") (pintype "output"))
      (node (ref "E34") (pin "6") (pinfunction "I0_6") (pintype "input"))
      (node (ref "E34") (pin "7") (pinfunction "I1_7") (pintype "input"))
    )
    (net (code "103") (name "Net-(E11A-CLK)") (class "Default")
      (node (ref "E11") (pin "3") (pinfunction "CLK_3") (pintype "input"))
      (node (ref "E11") (pin "9") (pinfunction "Q_9") (pintype "output"))
    )
    (net (code "104") (name "Net-(E12A-I)") (class "Default")
      (node (ref "D5") (pin "C") (pinfunction "C_C") (pintype "passive"))
      (node (ref "E12") (pin "1") (pinfunction "I_1") (pintype "input"))
      (node (ref "E13") (pin "5") (pinfunction "O_5") (pintype "open_collector"))
      (node (ref "R32") (pin "2") (pinfunction "2_2") (pintype "passive"))
    )
    (net (code "105") (name "Net-(E12A-O)") (class "Default")
      (node (ref "E12") (pin "2") (pinfunction "O_2") (pintype "output"))
      (node (ref "E15") (pin "2") (pinfunction "I1_2") (pintype "input"))
      (node (ref "E23") (pin "2") (pinfunction "I1_2") (pintype "input"))
    )
    (net (code "106") (name "Net-(E12B-O)") (class "Default")
      (node (ref "E12") (pin "4") (pinfunction "O_4") (pintype "output"))
      (node (ref "E13") (pin "6") (pinfunction "I0_6") (pintype "input"))
    )
    (net (code "107") (name "Net-(E12C-O)") (class "Default")
      (node (ref "E12") (pin "6") (pinfunction "O_6") (pintype "output"))
      (node (ref "E13") (pin "1") (pinfunction "I0_1") (pintype "input"))
    )
    (net (code "108") (name "Net-(E12D-O)") (class "Default")
      (node (ref "E12") (pin "8") (pinfunction "O_8") (pintype "output"))
      (node (ref "E18") (pin "10") (pinfunction "PRE_10") (pintype "input"))
      (node (ref "E18") (pin "11") (pinfunction "CLK_11") (pintype "input"))
      (node (ref "E18") (pin "12") (pinfunction "D_12") (pintype "input"))
      (node (ref "E18") (pin "13") (pinfunction "CLR_13") (pintype "input"))
    )
    (net (code "109") (name "Net-(E12E-I)") (class "Default")
      (node (ref "E12") (pin "11") (pinfunction "I_11") (pintype "input"))
      (node (ref "E23") (pin "12") (pinfunction "O_12") (pintype "output"))
      (node (ref "E23") (pin "9") (pinfunction "I0_9") (pintype "input"))
    )
    (net (code "110") (name "Net-(E12E-O)") (class "Default")
      (node (ref "E12") (pin "10") (pinfunction "O_10") (pintype "output"))
      (node (ref "E17") (pin "10") (pinfunction "I1_10") (pintype "input"))
      (node (ref "E17") (pin "12") (pinfunction "I0_12") (pintype "input"))
    )
    (net (code "111") (name "Net-(E12F-I)") (class "Default")
      (node (ref "C37") (pin "2") (pinfunction "2_2") (pintype "passive"))
      (node (ref "E12") (pin "13") (pinfunction "I_13") (pintype "input"))
      (node (ref "R22") (pin "1") (pinfunction "1_1") (pintype "passive"))
      (node (ref "R23") (pin "2") (pinfunction "2_2") (pintype "passive"))
    )
    (net (code "112") (name "Net-(E12F-O)") (class "Default")
      (node (ref "C37") (pin "1") (pinfunction "1_1") (pintype "passive"))
      (node (ref "E12") (pin "12") (pinfunction "O_12") (pintype "output"))
      (node (ref "E14") (pin "10") (pinfunction "B_10") (pintype "input"))
      (node (ref "E14") (pin "2") (pinfunction "B_2") (pintype "input"))
      (node (ref "E22") (pin "1") (pinfunction "I0_1") (pintype "input"))
    )
    (net (code "113") (name "Net-(E13A-O)") (class "Default")
      (node (ref "C36") (pin "1") (pinfunction "1_1") (pintype "passive"))
      (node (ref "E13") (pin "3") (pinfunction "O_3") (pintype "open_collector"))
      (node (ref "Q1") (pin "E") (pinfunction "E_E") (pintype "passive"))
      (node (ref "R20") (pin "1") (pinfunction "1_1") (pintype "passive"))
    )
    (net (code "114") (name "Net-(E13B-I1)") (class "Default")
      (node (ref "E13") (pin "7") (pinfunction "I1_7") (pintype "input"))
      (node (ref "E14") (pin "12") (pinfunction "~{Q}_12") (pintype "output"))
      (node (ref "E18") (pin "3") (pinfunction "CLK_3") (pintype "input"))
      (node (ref "E23") (pin "1") (pinfunction "I0_1") (pintype "input"))
    )
    (net (code "115") (name "Net-(E14A-C)") (class "Default")
      (node (ref "C35") (pin "2") (pinfunction "2_2") (pintype "passive"))
      (node (ref "E14") (pin "14") (pinfunction "C_14") (pintype "input"))
    )
    (net (code "116") (name "Net-(E14A-R{slash}C)") (class "Default")
      (node (ref "C35") (pin "1") (pinfunction "1_1") (pintype "passive"))
      (node (ref "E14") (pin "15") (pinfunction "R/C_15") (pintype "input"))
      (node (ref "R25") (pin "1") (pinfunction "1_1") (pintype "passive"))
    )
    (net (code "117") (name "Net-(E14A-~{Q})") (class "Default")
      (node (ref "E14") (pin "4") (pinfunction "~{Q}_4") (pintype "output"))
      (node (ref "E15") (pin "1") (pinfunction "I0_1") (pintype "input"))
    )
    (net (code "118") (name "Net-(E14B-C)") (class "Default")
      (node (ref "C25") (pin "2") (pinfunction "2_2") (pintype "passive"))
      (node (ref "E14") (pin "6") (pinfunction "C_6") (pintype "input"))
    )
    (net (code "119") (name "Net-(E14B-R{slash}C)") (class "Default")
      (node (ref "C25") (pin "1") (pinfunction "1_1") (pintype "passive"))
      (node (ref "E14") (pin "7") (pinfunction "R/C_7") (pintype "input"))
      (node (ref "R28") (pin "1") (pinfunction "1_1") (pintype "passive"))
    )
    (net (code "120") (name "Net-(E15A-O)") (class "Default")
      (node (ref "E15") (pin "3") (pinfunction "O_3") (pintype "output"))
      (node (ref "E16") (pin "11") (pinfunction "I2_11") (pintype "input"))
      (node (ref "E16") (pin "3") (pinfunction "I0_3") (pintype "input"))
    )
    (net (code "121") (name "Net-(E16A-I1)") (class "Default")
      (node (ref "E16") (pin "2") (pinfunction "I1_2") (pintype "input"))
      (node (ref "E17") (pin "11") (pinfunction "O_11") (pintype "output"))
    )
    (net (code "122") (name "Net-(E16A-O)") (class "Default")
      (node (ref "E16") (pin "12") (pinfunction "O_12") (pintype "output"))
      (node (ref "E19") (pin "14") (pinfunction "CLR_14") (pintype "input"))
      (node (ref "E20") (pin "14") (pinfunction "CLR_14") (pintype "input"))
    )
    (net (code "123") (name "Net-(E16B-O)") (class "Default")
      (node (ref "E16") (pin "6") (pinfunction "O_6") (pintype "output"))
      (node (ref "E19") (pin "5") (pinfunction "UP_5") (pintype "input"))
    )
    (net (code "124") (name "Net-(E16C-O)") (class "Default")
      (node (ref "E16") (pin "8") (pinfunction "O_8") (pintype "output"))
      (node (ref "E19") (pin "4") (pinfunction "DN_4") (pintype "input"))
    )
    (net (code "125") (name "Net-(E17A-I0)") (class "Default")
      (node (ref "E17") (pin "1") (pinfunction "I0_1") (pintype "input"))
      (node (ref "E17") (pin "6") (pinfunction "O_6") (pintype "output"))
    )
    (net (code "126") (name "Net-(E17A-O)") (class "Default")
      (node (ref "E17") (pin "3") (pinfunction "O_3") (pintype "output"))
      (node (ref "E17") (pin "4") (pinfunction "I0_4") (pintype "input"))
      (node (ref "E21") (pin "1") (pinfunction "I0_1") (pintype "input"))
    )
    (net (code "127") (name "Net-(E17C-O)") (class "Default")
      (node (ref "E17") (pin "8") (pinfunction "O_8") (pintype "output"))
      (node (ref "E19") (pin "11") (pinfunction "LD_11") (pintype "input"))
      (node (ref "E20") (pin "11") (pinfunction "LD_11") (pintype "input"))
    )
    (net (code "128") (name "Net-(E19A-BO)") (class "Default")
      (node (ref "E19") (pin "13") (pinfunction "BO_13") (pintype "output"))
      (node (ref "E20") (pin "4") (pinfunction "DN_4") (pintype "input"))
    )
    (net (code "129") (name "Net-(E19A-CO)") (class "Default")
      (node (ref "E19") (pin "12") (pinfunction "CO_12") (pintype "output"))
      (node (ref "E20") (pin "5") (pinfunction "UP_5") (pintype "input"))
    )
    (net (code "130") (name "Net-(E23A-I2)") (class "Default")
      (node (ref "E23") (pin "13") (pinfunction "I2_13") (pintype "input"))
      (node (ref "E23") (pin "8") (pinfunction "O_8") (pintype "output"))
    )
    (net (code "131") (name "Net-(E25-+IN)") (class "Default")
      (node (ref "E25") (pin "3") (pinfunction "+IN_3") (pintype "input"))
      (node (ref "R30") (pin "1") (pinfunction "1_1") (pintype "passive"))
      (node (ref "R31") (pin "2") (pinfunction "2_2") (pintype "passive"))
    )
    (net (code "132") (name "Net-(E25--IN)") (class "Default")
      (node (ref "C38") (pin "1") (pinfunction "1_1") (pintype "passive"))
      (node (ref "E25") (pin "2") (pinfunction "-IN_2") (pintype "input"))
      (node (ref "R29") (pin "1") (pinfunction "1_1") (pintype "passive"))
    )
    (net (code "133") (name "Net-(E25-OUT)") (class "Default")
      (node (ref "E25") (pin "6") (pinfunction "OUT_6") (pintype "output"))
      (node (ref "R29") (pin "2") (pinfunction "2_2") (pintype "passive"))
      (node (ref "R30") (pin "2") (pinfunction "2_2") (pintype "passive"))
      (node (ref "R32") (pin "1") (pinfunction "1_1") (pintype "passive"))
    )
    (net (code "134") (name "Net-(E26A-O)") (class "Default")
      (node (ref "E26") (pin "3") (pinfunction "O_3") (pintype "output"))
      (node (ref "E30") (pin "2") (pinfunction "I1_2") (pintype "input"))
    )
    (net (code "135") (name "Net-(E26B-O)") (class "Default")
      (node (ref "E26") (pin "6") (pinfunction "O_6") (pintype "output"))
      (node (ref "E30") (pin "7") (pinfunction "I1_7") (pintype "input"))
    )
    (net (code "136") (name "Net-(E26C-O)") (class "Default")
      (node (ref "E26") (pin "8") (pinfunction "O_8") (pintype "output"))
      (node (ref "E30") (pin "6") (pinfunction "I0_6") (pintype "input"))
    )
    (net (code "137") (name "Net-(E26D-O)") (class "Default")
      (node (ref "E26") (pin "11") (pinfunction "O_11") (pintype "output"))
      (node (ref "E30") (pin "1") (pinfunction "I0_1") (pintype "input"))
    )
    (net (code "138") (name "Net-(E27A-O)") (class "Default")
      (node (ref "E27") (pin "3") (pinfunction "O_3") (pintype "output"))
      (node (ref "E31") (pin "2") (pinfunction "I1_2") (pintype "input"))
    )
    (net (code "139") (name "Net-(E27B-O)") (class "Default")
      (node (ref "E27") (pin "6") (pinfunction "O_6") (pintype "output"))
      (node (ref "E31") (pin "7") (pinfunction "I1_7") (pintype "input"))
    )
    (net (code "140") (name "Net-(E27C-O)") (class "Default")
      (node (ref "E27") (pin "8") (pinfunction "O_8") (pintype "output"))
      (node (ref "E31") (pin "6") (pinfunction "I0_6") (pintype "input"))
    )
    (net (code "141") (name "Net-(E27D-O)") (class "Default")
      (node (ref "E27") (pin "11") (pinfunction "O_11") (pintype "output"))
      (node (ref "E31") (pin "1") (pinfunction "I0_1") (pintype "input"))
    )
    (net (code "142") (name "Net-(E28A-O)") (class "Default")
      (node (ref "E28") (pin "3") (pinfunction "O_3") (pintype "output"))
      (node (ref "E32") (pin "2") (pinfunction "I1_2") (pintype "input"))
    )
    (net (code "143") (name "Net-(E28B-O)") (class "Default")
      (node (ref "E28") (pin "6") (pinfunction "O_6") (pintype "output"))
      (node (ref "E32") (pin "7") (pinfunction "I1_7") (pintype "input"))
    )
    (net (code "144") (name "Net-(E28C-O)") (class "Default")
      (node (ref "E28") (pin "8") (pinfunction "O_8") (pintype "output"))
      (node (ref "E32") (pin "6") (pinfunction "I0_6") (pintype "input"))
    )
    (net (code "145") (name "Net-(E28D-O)") (class "Default")
      (node (ref "E28") (pin "11") (pinfunction "O_11") (pintype "output"))
      (node (ref "E32") (pin "1") (pinfunction "I0_1") (pintype "input"))
    )
    (net (code "146") (name "Net-(E29A-O)") (class "Default")
      (node (ref "E29") (pin "3") (pinfunction "O_3") (pintype "output"))
      (node (ref "E33") (pin "2") (pinfunction "I1_2") (pintype "input"))
    )
    (net (code "147") (name "Net-(E29B-O)") (class "Default")
      (node (ref "E29") (pin "6") (pinfunction "O_6") (pintype "output"))
      (node (ref "E33") (pin "7") (pinfunction "I1_7") (pintype "input"))
    )
    (net (code "148") (name "Net-(E29C-O)") (class "Default")
      (node (ref "E29") (pin "8") (pinfunction "O_8") (pintype "output"))
      (node (ref "E33") (pin "6") (pinfunction "I0_6") (pintype "input"))
    )
    (net (code "149") (name "Net-(E29D-O)") (class "Default")
      (node (ref "E29") (pin "11") (pinfunction "O_11") (pintype "output"))
      (node (ref "E33") (pin "1") (pinfunction "I0_1") (pintype "input"))
    )
    (net (code "150") (name "Net-(POWER_ON-PadA)") (class "Default")
      (node (ref "POWER_ON") (pin "A") (pinfunction "A_A") (pintype "passive"))
      (node (ref "R3") (pin "1") (pinfunction "1_1") (pintype "passive"))
    )
    (net (code "151") (name "Net-(Q1-PadB1)") (class "Default")
      (node (ref "Q1") (pin "B1") (pinfunction "B1_B1") (pintype "passive"))
      (node (ref "R21") (pin "1") (pinfunction "1_1") (pintype "passive"))
    )
    (net (code "152") (name "Net-(Q1-PadB2)") (class "Default")
      (node (ref "Q1") (pin "B2") (pinfunction "B2_B2") (pintype "passive"))
      (node (ref "R22") (pin "2") (pinfunction "2_2") (pintype "passive"))
    )
    (net (code "153") (name "Net-(R2-Pad1)") (class "Default")
      (node (ref "R2") (pin "1") (pinfunction "1_1") (pintype "passive"))
      (node (ref "SEEK_INC") (pin "A") (pinfunction "A_A") (pintype "passive"))
    )
    (net (code "154") (name "Net-(RTZA-O)") (class "Default")
      (node (ref "RTZ") (pin "1") (pinfunction "O_1") (pintype "passive"))
      (node (ref "RUN") (pin "2") (pinfunction "P_2") (pintype "passive"))
    )
    (net (code "155") (name "OSC_L") (class "Default")
      (node (ref "E16") (pin "13") (pinfunction "I2_13") (pintype "input"))
      (node (ref "FUNCTION") (pin "3") (pinfunction "3_3") (pintype "passive"))
      (node (ref "R35") (pin "1") (pinfunction "1_1") (pintype "passive"))
    )
    (net (code "156") (name "RANDOM_L") (class "Default")
      (node (ref "D1") (pin "C") (pinfunction "C_C") (pintype "passive"))
      (node (ref "E12") (pin "3") (pinfunction "I_3") (pintype "input"))
      (node (ref "FUNCTION") (pin "4") (pinfunction "4_4") (pintype "passive"))
      (node (ref "R34") (pin "1") (pinfunction "1_1") (pintype "passive"))
    )
    (net (code "157") (name "READ_CLOCK") (class "Default")
      (node (ref "J1") (pin "F") (pinfunction "P$2_F") (pintype "bidirectional"))
      (node (ref "RN1") (pin "3") (pinfunction "2_3") (pintype "passive"))
      (node (ref "RN5") (pin "3") (pinfunction "2_3") (pintype "passive"))
    )
    (net (code "158") (name "READ_DATA") (class "Default")
      (node (ref "J1") (pin "D") (pinfunction "P$2_D") (pintype "bidirectional"))
      (node (ref "RN1") (pin "2") (pinfunction "2_2") (pintype "passive"))
      (node (ref "RN5") (pin "2") (pinfunction "2_2") (pintype "passive"))
    )
    (net (code "159") (name "REV_L") (class "Default")
      (node (ref "E16") (pin "5") (pinfunction "I2_5") (pintype "input"))
      (node (ref "E17") (pin "13") (pinfunction "I1_13") (pintype "input"))
      (node (ref "FWD/REV") (pin "1") (pinfunction "O_1") (pintype "passive"))
      (node (ref "R33") (pin "1") (pinfunction "1_1") (pintype "passive"))
    )
    (net (code "160") (name "RK05_AU2") (class "Default")
      (node (ref "J2") (pin "A") (pinfunction "P$2_A") (pintype "bidirectional"))
      (node (ref "RN3") (pin "2") (pinfunction "2_2") (pintype "passive"))
      (node (ref "RN7") (pin "2") (pinfunction "2_2") (pintype "passive"))
    )
    (net (code "161") (name "RK05_BH2") (class "Default")
      (node (ref "J1") (pin "NN") (pinfunction "P$2_NN") (pintype "bidirectional"))
      (node (ref "RN2") (pin "4") (pinfunction "2_4") (pintype "passive"))
      (node (ref "RN6") (pin "4") (pinfunction "2_4") (pintype "passive"))
    )
    (net (code "162") (name "RTZ_L") (class "Default")
      (node (ref "E16") (pin "1") (pinfunction "I0_1") (pintype "input"))
      (node (ref "E17") (pin "2") (pinfunction "I1_2") (pintype "input"))
      (node (ref "E22") (pin "7") (pinfunction "I1_7") (pintype "input"))
      (node (ref "R24") (pin "1") (pinfunction "1_1") (pintype "passive"))
      (node (ref "RTZ") (pin "3") (pinfunction "S_3") (pintype "passive"))
    )
    (net (code "163") (name "RUN_L") (class "Default")
      (node (ref "E13") (pin "2") (pinfunction "I1_2") (pintype "input"))
      (node (ref "R19") (pin "1") (pinfunction "1_1") (pintype "passive"))
      (node (ref "RUN") (pin "1") (pinfunction "O_1") (pintype "passive"))
    )
    (net (code "164") (name "SECTOR_0L") (class "Default")
      (node (ref "E3") (pin "1") (pinfunction "O0_1") (pintype "output"))
      (node (ref "SECTOR") (pin "1") (pinfunction "1_1") (pintype "passive"))
    )
    (net (code "165") (name "SECTOR_1L") (class "Default")
      (node (ref "E3") (pin "2") (pinfunction "O1_2") (pintype "output"))
      (node (ref "SECTOR") (pin "2") (pinfunction "2_2") (pintype "passive"))
    )
    (net (code "166") (name "SECTOR_2L") (class "Default")
      (node (ref "E3") (pin "3") (pinfunction "O2_3") (pintype "output"))
      (node (ref "SECTOR") (pin "3") (pinfunction "3_3") (pintype "passive"))
    )
    (net (code "167") (name "SECTOR_3L") (class "Default")
      (node (ref "E3") (pin "4") (pinfunction "O3_4") (pintype "output"))
      (node (ref "SECTOR") (pin "4") (pinfunction "4_4") (pintype "passive"))
    )
    (net (code "168") (name "SECTOR_4L") (class "Default")
      (node (ref "E3") (pin "5") (pinfunction "O4_5") (pintype "output"))
      (node (ref "SECTOR") (pin "5") (pinfunction "5_5") (pintype "passive"))
    )
    (net (code "169") (name "SECTOR_5L") (class "Default")
      (node (ref "E3") (pin "6") (pinfunction "O5_6") (pintype "output"))
      (node (ref "SECTOR") (pin "6") (pinfunction "6_6") (pintype "passive"))
    )
    (net (code "170") (name "SECTOR_6L") (class "Default")
      (node (ref "E3") (pin "7") (pinfunction "O6_7") (pintype "output"))
      (node (ref "SECTOR") (pin "7") (pinfunction "7_7") (pintype "passive"))
    )
    (net (code "171") (name "SECTOR_7L") (class "Default")
      (node (ref "E3") (pin "9") (pinfunction "O7_9") (pintype "output"))
      (node (ref "SECTOR") (pin "8") (pinfunction "8_8") (pintype "passive"))
    )
    (net (code "172") (name "SECTOR_8L") (class "Default")
      (node (ref "E3") (pin "10") (pinfunction "O8_10") (pintype "output"))
      (node (ref "SECTOR") (pin "9") (pinfunction "9_9") (pintype "passive"))
    )
    (net (code "173") (name "SECTOR_9L") (class "Default")
      (node (ref "E3") (pin "11") (pinfunction "O9_11") (pintype "output"))
      (node (ref "SECTOR") (pin "10") (pinfunction "10_10") (pintype "passive"))
    )
    (net (code "174") (name "SECTOR_SELECT_L") (class "Default")
      (node (ref "E7") (pin "1") (pinfunction "I0_1") (pintype "input"))
      (node (ref "SECTOR") (pin "A") (pinfunction "A_A") (pintype "passive"))
    )
    (net (code "175") (name "SEEK_INCOMPLETE_L") (class "Default")
      (node (ref "E21") (pin "3") (pinfunction "O_3") (pintype "open_collector"))
      (node (ref "SEEK_INC") (pin "B") (pinfunction "B_B") (pintype "passive"))
    )
    (net (code "176") (name "SELECT_0L") (class "Default")
      (node (ref "DRIVE") (pin "1") (pinfunction "1_1") (pintype "passive"))
      (node (ref "J2") (pin "AA") (pinfunction "P$2_AA") (pintype "bidirectional"))
      (node (ref "RN4") (pin "10") (pinfunction "2_10") (pintype "passive"))
      (node (ref "RN8") (pin "10") (pinfunction "2_10") (pintype "passive"))
    )
    (net (code "177") (name "SELECT_1L") (class "Default")
      (node (ref "DRIVE") (pin "2") (pinfunction "2_2") (pintype "passive"))
      (node (ref "J2") (pin "W") (pinfunction "P$2_W") (pintype "bidirectional"))
      (node (ref "R69") (pin "1") (pinfunction "1_1") (pintype "passive"))
      (node (ref "R70") (pin "2") (pinfunction "2_2") (pintype "passive"))
    )
    (net (code "178") (name "SELECT_2L") (class "Default")
      (node (ref "DRIVE") (pin "3") (pinfunction "3_3") (pintype "passive"))
      (node (ref "J2") (pin "S") (pinfunction "P$2_S") (pintype "bidirectional"))
      (node (ref "RN3") (pin "9") (pinfunction "2_9") (pintype "passive"))
      (node (ref "RN7") (pin "9") (pinfunction "2_9") (pintype "passive"))
    )
    (net (code "179") (name "SELECT_3L") (class "Default")
      (node (ref "DRIVE") (pin "4") (pinfunction "4_4") (pintype "passive"))
      (node (ref "J2") (pin "M") (pinfunction "P$2_M") (pintype "bidirectional"))
      (node (ref "RN3") (pin "7") (pinfunction "2_7") (pintype "passive"))
      (node (ref "RN7") (pin "7") (pinfunction "2_7") (pintype "passive"))
    )
    (net (code "180") (name "STEP_L") (class "Default")
      (node (ref "D1") (pin "A") (pinfunction "A_A") (pintype "passive"))
      (node (ref "E18") (pin "1") (pinfunction "CLR_1") (pintype "input"))
      (node (ref "FUNCTION") (pin "1") (pinfunction "1_1") (pintype "passive"))
      (node (ref "R37") (pin "1") (pinfunction "1_1") (pintype "passive"))
    )
    (net (code "181") (name "VCC") (class "Default")
      (node (ref "C1") (pin "1") (pinfunction "1_1") (pintype "passive"))
      (node (ref "C10") (pin "1") (pinfunction "1_1") (pintype "passive"))
      (node (ref "C11") (pin "1") (pinfunction "1_1") (pintype "passive"))
      (node (ref "C12") (pin "1") (pinfunction "1_1") (pintype "passive"))
      (node (ref "C13") (pin "1") (pinfunction "1_1") (pintype "passive"))
      (node (ref "C14") (pin "1") (pinfunction "1_1") (pintype "passive"))
      (node (ref "C15") (pin "1") (pinfunction "1_1") (pintype "passive"))
      (node (ref "C16") (pin "1") (pinfunction "1_1") (pintype "passive"))
      (node (ref "C17") (pin "1") (pinfunction "1_1") (pintype "passive"))
      (node (ref "C18") (pin "1") (pinfunction "1_1") (pintype "passive"))
      (node (ref "C19") (pin "1") (pinfunction "1_1") (pintype "passive"))
      (node (ref "C2") (pin "1") (pinfunction "1_1") (pintype "passive"))
      (node (ref "C20") (pin "1") (pinfunction "1_1") (pintype "passive"))
      (node (ref "C21") (pin "1") (pinfunction "1_1") (pintype "passive"))
      (node (ref "C22") (pin "1") (pinfunction "1_1") (pintype "passive"))
      (node (ref "C23") (pin "1") (pinfunction "1_1") (pintype "passive"))
      (node (ref "C24") (pin "1") (pinfunction "1_1") (pintype "passive"))
      (node (ref "C26") (pin "1") (pinfunction "1_1") (pintype "passive"))
      (node (ref "C27") (pin "1") (pinfunction "1_1") (pintype "passive"))
      (node (ref "C28") (pin "1") (pinfunction "1_1") (pintype "passive"))
      (node (ref "C29") (pin "1") (pinfunction "1_1") (pintype "passive"))
      (node (ref "C3") (pin "1") (pinfunction "1_1") (pintype "passive"))
      (node (ref "C30") (pin "1") (pinfunction "1_1") (pintype "passive"))
      (node (ref "C31") (pin "1") (pinfunction "1_1") (pintype "passive"))
      (node (ref "C32") (pin "1") (pinfunction "1_1") (pintype "passive"))
      (node (ref "C33") (pin "1") (pinfunction "1_1") (pintype "passive"))
      (node (ref "C4") (pin "1") (pinfunction "1_1") (pintype "passive"))
      (node (ref "C40") (pin "1") (pinfunction "1_1") (pintype "passive"))
      (node (ref "C41") (pin "1") (pinfunction "1_1") (pintype "passive"))
      (node (ref "C42") (pin "1") (pinfunction "1_1") (pintype "passive"))
      (node (ref "C43") (pin "1") (pinfunction "1_1") (pintype "passive"))
      (node (ref "C5") (pin "1") (pinfunction "1_1") (pintype "passive"))
      (node (ref "C52") (pin "+") (pinfunction "+_+") (pintype "passive"))
      (node (ref "C6") (pin "1") (pinfunction "1_1") (pintype "passive"))
      (node (ref "C60") (pin "+") (pinfunction "+_+") (pintype "passive"))
      (node (ref "C61") (pin "+") (pinfunction "+_+") (pintype "passive"))
      (node (ref "C67") (pin "+") (pinfunction "+_+") (pintype "passive"))
      (node (ref "C68") (pin "+") (pinfunction "+_+") (pintype "passive"))
      (node (ref "C7") (pin "1") (pinfunction "1_1") (pintype "passive"))
      (node (ref "C8") (pin "1") (pinfunction "1_1") (pintype "passive"))
      (node (ref "C9") (pin "1") (pinfunction "1_1") (pintype "passive"))
      (node (ref "D2") (pin "A") (pinfunction "A_A") (pintype "passive"))
      (node (ref "E5") (pin "1") (pinfunction "CLR_1") (pintype "input"))
      (node (ref "E5") (pin "4") (pinfunction "PRE_4") (pintype "input"))
      (node (ref "POWER") (pin "2") (pinfunction "2_2") (pintype "passive"))
      (node (ref "R10") (pin "2") (pinfunction "2_2") (pintype "passive"))
      (node (ref "R11") (pin "2") (pinfunction "2_2") (pintype "passive"))
      (node (ref "R12") (pin "2") (pinfunction "2_2") (pintype "passive"))
      (node (ref "R13") (pin "2") (pinfunction "2_2") (pintype "passive"))
      (node (ref "R147") (pin "2") (pinfunction "2_2") (pintype "passive"))
      (node (ref "R16") (pin "2") (pinfunction "2_2") (pintype "passive"))
      (node (ref "R17") (pin "2") (pinfunction "2_2") (pintype "passive"))
      (node (ref "R18") (pin "2") (pinfunction "2_2") (pintype "passive"))
      (node (ref "R19") (pin "2") (pinfunction "2_2") (pintype "passive"))
      (node (ref "R24") (pin "2") (pinfunction "2_2") (pintype "passive"))
      (node (ref "R25") (pin "2") (pinfunction "2_2") (pintype "passive"))
      (node (ref "R26") (pin "2") (pinfunction "2_2") (pintype "passive"))
      (node (ref "R27") (pin "2") (pinfunction "2_2") (pintype "passive"))
      (node (ref "R28") (pin "2") (pinfunction "2_2") (pintype "passive"))
      (node (ref "R33") (pin "2") (pinfunction "2_2") (pintype "passive"))
      (node (ref "R34") (pin "2") (pinfunction "2_2") (pintype "passive"))
      (node (ref "R35") (pin "2") (pinfunction "2_2") (pintype "passive"))
      (node (ref "R36") (pin "2") (pinfunction "2_2") (pintype "passive"))
      (node (ref "R37") (pin "2") (pinfunction "2_2") (pintype "passive"))
      (node (ref "R38") (pin "1") (pinfunction "1_1") (pintype "passive"))
      (node (ref "R39") (pin "1") (pinfunction "1_1") (pintype "passive"))
      (node (ref "R4") (pin "2") (pinfunction "2_2") (pintype "passive"))
      (node (ref "R40") (pin "1") (pinfunction "1_1") (pintype "passive"))
      (node (ref "R41") (pin "1") (pinfunction "1_1") (pintype "passive"))
      (node (ref "R42") (pin "1") (pinfunction "1_1") (pintype "passive"))
      (node (ref "R43") (pin "1") (pinfunction "1_1") (pintype "passive"))
      (node (ref "R44") (pin "1") (pinfunction "1_1") (pintype "passive"))
      (node (ref "R45") (pin "1") (pinfunction "1_1") (pintype "passive"))
      (node (ref "R46") (pin "2") (pinfunction "2_2") (pintype "passive"))
      (node (ref "R5") (pin "2") (pinfunction "2_2") (pintype "passive"))
      (node (ref "R50") (pin "2") (pinfunction "2_2") (pintype "passive"))
      (node (ref "R6") (pin "2") (pinfunction "2_2") (pintype "passive"))
      (node (ref "R69") (pin "2") (pinfunction "2_2") (pintype "passive"))
      (node (ref "R7") (pin "2") (pinfunction "2_2") (pintype "passive"))
      (node (ref "R8") (pin "2") (pinfunction "2_2") (pintype "passive"))
      (node (ref "R9") (pin "A") (pinfunction "A_A") (pintype "passive"))
      (node (ref "RN1") (pin "1") (pinfunction "1_1") (pintype "passive"))
      (node (ref "RN2") (pin "1") (pinfunction "1_1") (pintype "passive"))
      (node (ref "RN2") (pin "2") (pinfunction "2_2") (pintype "passive"))
      (node (ref "RN3") (pin "1") (pinfunction "1_1") (pintype "passive"))
      (node (ref "RN4") (pin "1") (pinfunction "1_1") (pintype "passive"))
    )
    (net (code "182") (name "WRITE_GATE") (class "Default")
      (node (ref "E10") (pin "12") (pinfunction "I0_12") (pintype "input"))
      (node (ref "E11") (pin "5") (pinfunction "Q_5") (pintype "output"))
      (node (ref "E2") (pin "1") (pinfunction "CLR_1") (pintype "input"))
      (node (ref "E2") (pin "13") (pinfunction "CLR_13") (pintype "input"))
      (node (ref "E5") (pin "13") (pinfunction "CLR_13") (pintype "input"))
      (node (ref "E8") (pin "11") (pinfunction "CLR_11") (pintype "input"))
      (node (ref "E8") (pin "2") (pinfunction "B_2") (pintype "input"))
      (node (ref "E8") (pin "3") (pinfunction "CLR_3") (pintype "input"))
    )
    (net (code "183") (name "WRITE_H") (class "Default")
      (node (ref "E10") (pin "4") (pinfunction "I0_4") (pintype "input"))
      (node (ref "R5") (pin "1") (pinfunction "1_1") (pintype "passive"))
      (node (ref "WRITE") (pin "1") (pinfunction "O_1") (pintype "passive"))
    )
    (net (code "184") (name "WRITE_L") (class "Default")
      (node (ref "E10") (pin "1") (pinfunction "I0_1") (pintype "input"))
      (node (ref "R6") (pin "1") (pinfunction "1_1") (pintype "passive"))
      (node (ref "WRITE") (pin "3") (pinfunction "S_3") (pintype "passive"))
    )
    (net (code "185") (name "unconnected-(CYL1A-O-Pad1)") (class "Default")
      (node (ref "CYL1") (pin "1") (pinfunction "O_1") (pintype "passive"))
    )
    (net (code "186") (name "unconnected-(CYL2A-O-Pad1)") (class "Default")
      (node (ref "CYL2") (pin "1") (pinfunction "O_1") (pintype "passive"))
    )
    (net (code "187") (name "unconnected-(CYL4A-O-Pad1)") (class "Default")
      (node (ref "CYL4") (pin "1") (pinfunction "O_1") (pintype "passive"))
    )
    (net (code "188") (name "unconnected-(CYL8A-O-Pad1)") (class "Default")
      (node (ref "CYL8") (pin "1") (pinfunction "O_1") (pintype "passive"))
    )
    (net (code "189") (name "unconnected-(CYL16A-O-Pad1)") (class "Default")
      (node (ref "CYL16") (pin "1") (pinfunction "O_1") (pintype "passive"))
    )
    (net (code "190") (name "unconnected-(CYL32A-O-Pad1)") (class "Default")
      (node (ref "CYL32") (pin "1") (pinfunction "O_1") (pintype "passive"))
    )
    (net (code "191") (name "unconnected-(CYL64A-O-Pad1)") (class "Default")
      (node (ref "CYL64") (pin "1") (pinfunction "O_1") (pintype "passive"))
    )
    (net (code "192") (name "unconnected-(CYL128A-O-Pad1)") (class "Default")
      (node (ref "CYL128") (pin "1") (pinfunction "O_1") (pintype "passive"))
    )
    (net (code "193") (name "unconnected-(DRIVE-Pad5)") (class "Default")
      (node (ref "DRIVE") (pin "5") (pinfunction "5_5") (pintype "passive"))
    )
    (net (code "194") (name "unconnected-(DRIVE-Pad6)") (class "Default")
      (node (ref "DRIVE") (pin "6") (pinfunction "6_6") (pintype "passive"))
    )
    (net (code "195") (name "unconnected-(DRIVE-Pad7)") (class "Default")
      (node (ref "DRIVE") (pin "7") (pinfunction "7_7") (pintype "passive"))
    )
    (net (code "196") (name "unconnected-(DRIVE-Pad8)") (class "Default")
      (node (ref "DRIVE") (pin "8") (pinfunction "8_8") (pintype "passive"))
    )
    (net (code "197") (name "unconnected-(DRIVE-Pad9)") (class "Default")
      (node (ref "DRIVE") (pin "9") (pinfunction "9_9") (pintype "passive"))
    )
    (net (code "198") (name "unconnected-(DRIVE-Pad10)") (class "Default")
      (node (ref "DRIVE") (pin "10") (pinfunction "10_10") (pintype "passive"))
    )
    (net (code "199") (name "unconnected-(DRIVE-Pad11)") (class "Default")
      (node (ref "DRIVE") (pin "11") (pinfunction "11_11") (pintype "passive"))
    )
    (net (code "200") (name "unconnected-(DRIVE-Pad12)") (class "Default")
      (node (ref "DRIVE") (pin "12") (pinfunction "12_12") (pintype "passive"))
    )
    (net (code "201") (name "unconnected-(E5A-Q-Pad5)") (class "Default")
      (node (ref "E5") (pin "5") (pinfunction "Q_5") (pintype "output"))
    )
    (net (code "202") (name "unconnected-(E5A-~{Q}-Pad6)") (class "Default")
      (node (ref "E5") (pin "6") (pinfunction "~{Q}_6") (pintype "output"))
    )
    (net (code "203") (name "unconnected-(E5B-Q-Pad9)") (class "Default")
      (node (ref "E5") (pin "9") (pinfunction "Q_9") (pintype "output"))
    )
    (net (code "204") (name "unconnected-(E8A-Q-Pad13)") (class "Default")
      (node (ref "E8") (pin "13") (pinfunction "Q_13") (pintype "output"))
    )
    (net (code "205") (name "unconnected-(E11A-~{Q}-Pad6)") (class "Default")
      (node (ref "E11") (pin "6") (pinfunction "~{Q}_6") (pintype "output"))
    )
    (net (code "206") (name "unconnected-(E11B-~{Q}-Pad8)") (class "Default")
      (node (ref "E11") (pin "8") (pinfunction "~{Q}_8") (pintype "output"))
    )
    (net (code "207") (name "unconnected-(E14A-Q-Pad13)") (class "Default")
      (node (ref "E14") (pin "13") (pinfunction "Q_13") (pintype "output"))
    )
    (net (code "208") (name "unconnected-(E14B-Q-Pad5)") (class "Default")
      (node (ref "E14") (pin "5") (pinfunction "Q_5") (pintype "output"))
    )
    (net (code "209") (name "unconnected-(E15B-O-Pad6)") (class "Default")
      (node (ref "E15") (pin "6") (pinfunction "O_6") (pintype "output"))
    )
    (net (code "210") (name "unconnected-(E15C-O-Pad8)") (class "Default")
      (node (ref "E15") (pin "8") (pinfunction "O_8") (pintype "output"))
    )
    (net (code "211") (name "unconnected-(E15D-O-Pad11)") (class "Default")
      (node (ref "E15") (pin "11") (pinfunction "O_11") (pintype "output"))
    )
    (net (code "212") (name "unconnected-(E18B-Q-Pad9)") (class "Default")
      (node (ref "E18") (pin "9") (pinfunction "Q_9") (pintype "output"))
    )
    (net (code "213") (name "unconnected-(E18B-~{Q}-Pad8)") (class "Default")
      (node (ref "E18") (pin "8") (pinfunction "~{Q}_8") (pintype "output"))
    )
    (net (code "214") (name "unconnected-(E20A-BO-Pad13)") (class "Default")
      (node (ref "E20") (pin "13") (pinfunction "BO_13") (pintype "output"))
    )
    (net (code "215") (name "unconnected-(E20A-CO-Pad12)") (class "Default")
      (node (ref "E20") (pin "12") (pinfunction "CO_12") (pintype "output"))
    )
    (net (code "216") (name "unconnected-(E24B-O-Pad8)") (class "Default")
      (node (ref "E24") (pin "8") (pinfunction "O_8") (pintype "output"))
    )
    (net (code "217") (name "unconnected-(E25-ON1-Pad1)") (class "Default")
      (node (ref "E25") (pin "1") (pinfunction "ON1_1") (pintype "passive"))
    )
    (net (code "218") (name "unconnected-(E25-ON2-Pad5)") (class "Default")
      (node (ref "E25") (pin "5") (pinfunction "ON2_5") (pintype "passive"))
    )
    (net (code "219") (name "unconnected-(E25-OPT-Pad8)") (class "Default")
      (node (ref "E25") (pin "8") (pinfunction "OPT_8") (pintype "passive"))
    )
    (net (code "220") (name "unconnected-(FUNCTION-Pad2)") (class "Default")
      (node (ref "FUNCTION") (pin "2") (pinfunction "2_2") (pintype "passive"))
    )
    (net (code "221") (name "unconnected-(FUNCTION-Pad5)") (class "Default")
      (node (ref "FUNCTION") (pin "5") (pinfunction "5_5") (pintype "passive"))
    )
    (net (code "222") (name "unconnected-(FUNCTION-Pad6)") (class "Default")
      (node (ref "FUNCTION") (pin "6") (pinfunction "6_6") (pintype "passive"))
    )
    (net (code "223") (name "unconnected-(FUNCTION-Pad7)") (class "Default")
      (node (ref "FUNCTION") (pin "7") (pinfunction "7_7") (pintype "passive"))
    )
    (net (code "224") (name "unconnected-(FUNCTION-Pad8)") (class "Default")
      (node (ref "FUNCTION") (pin "8") (pinfunction "8_8") (pintype "passive"))
    )
    (net (code "225") (name "unconnected-(FUNCTION-Pad9)") (class "Default")
      (node (ref "FUNCTION") (pin "9") (pinfunction "9_9") (pintype "passive"))
    )
    (net (code "226") (name "unconnected-(FUNCTION-Pad10)") (class "Default")
      (node (ref "FUNCTION") (pin "10") (pinfunction "10_10") (pintype "passive"))
    )
    (net (code "227") (name "unconnected-(FUNCTION-Pad11)") (class "Default")
      (node (ref "FUNCTION") (pin "11") (pinfunction "11_11") (pintype "passive"))
    )
    (net (code "228") (name "unconnected-(FUNCTION-Pad12)") (class "Default")
      (node (ref "FUNCTION") (pin "12") (pinfunction "12_12") (pintype "passive"))
    )
    (net (code "229") (name "unconnected-(HEADA-O-Pad1)") (class "Default")
      (node (ref "HEAD") (pin "1") (pinfunction "O_1") (pintype "passive"))
    )
    (net (code "230") (name "unconnected-(RUNA-S-Pad3)") (class "Default")
      (node (ref "RUN") (pin "3") (pinfunction "S_3") (pintype "passive"))
    )
  )
)
